# ELC0102_-_Green_Digits.net
KiCad netlist of a schematic drawn in Altium Designer
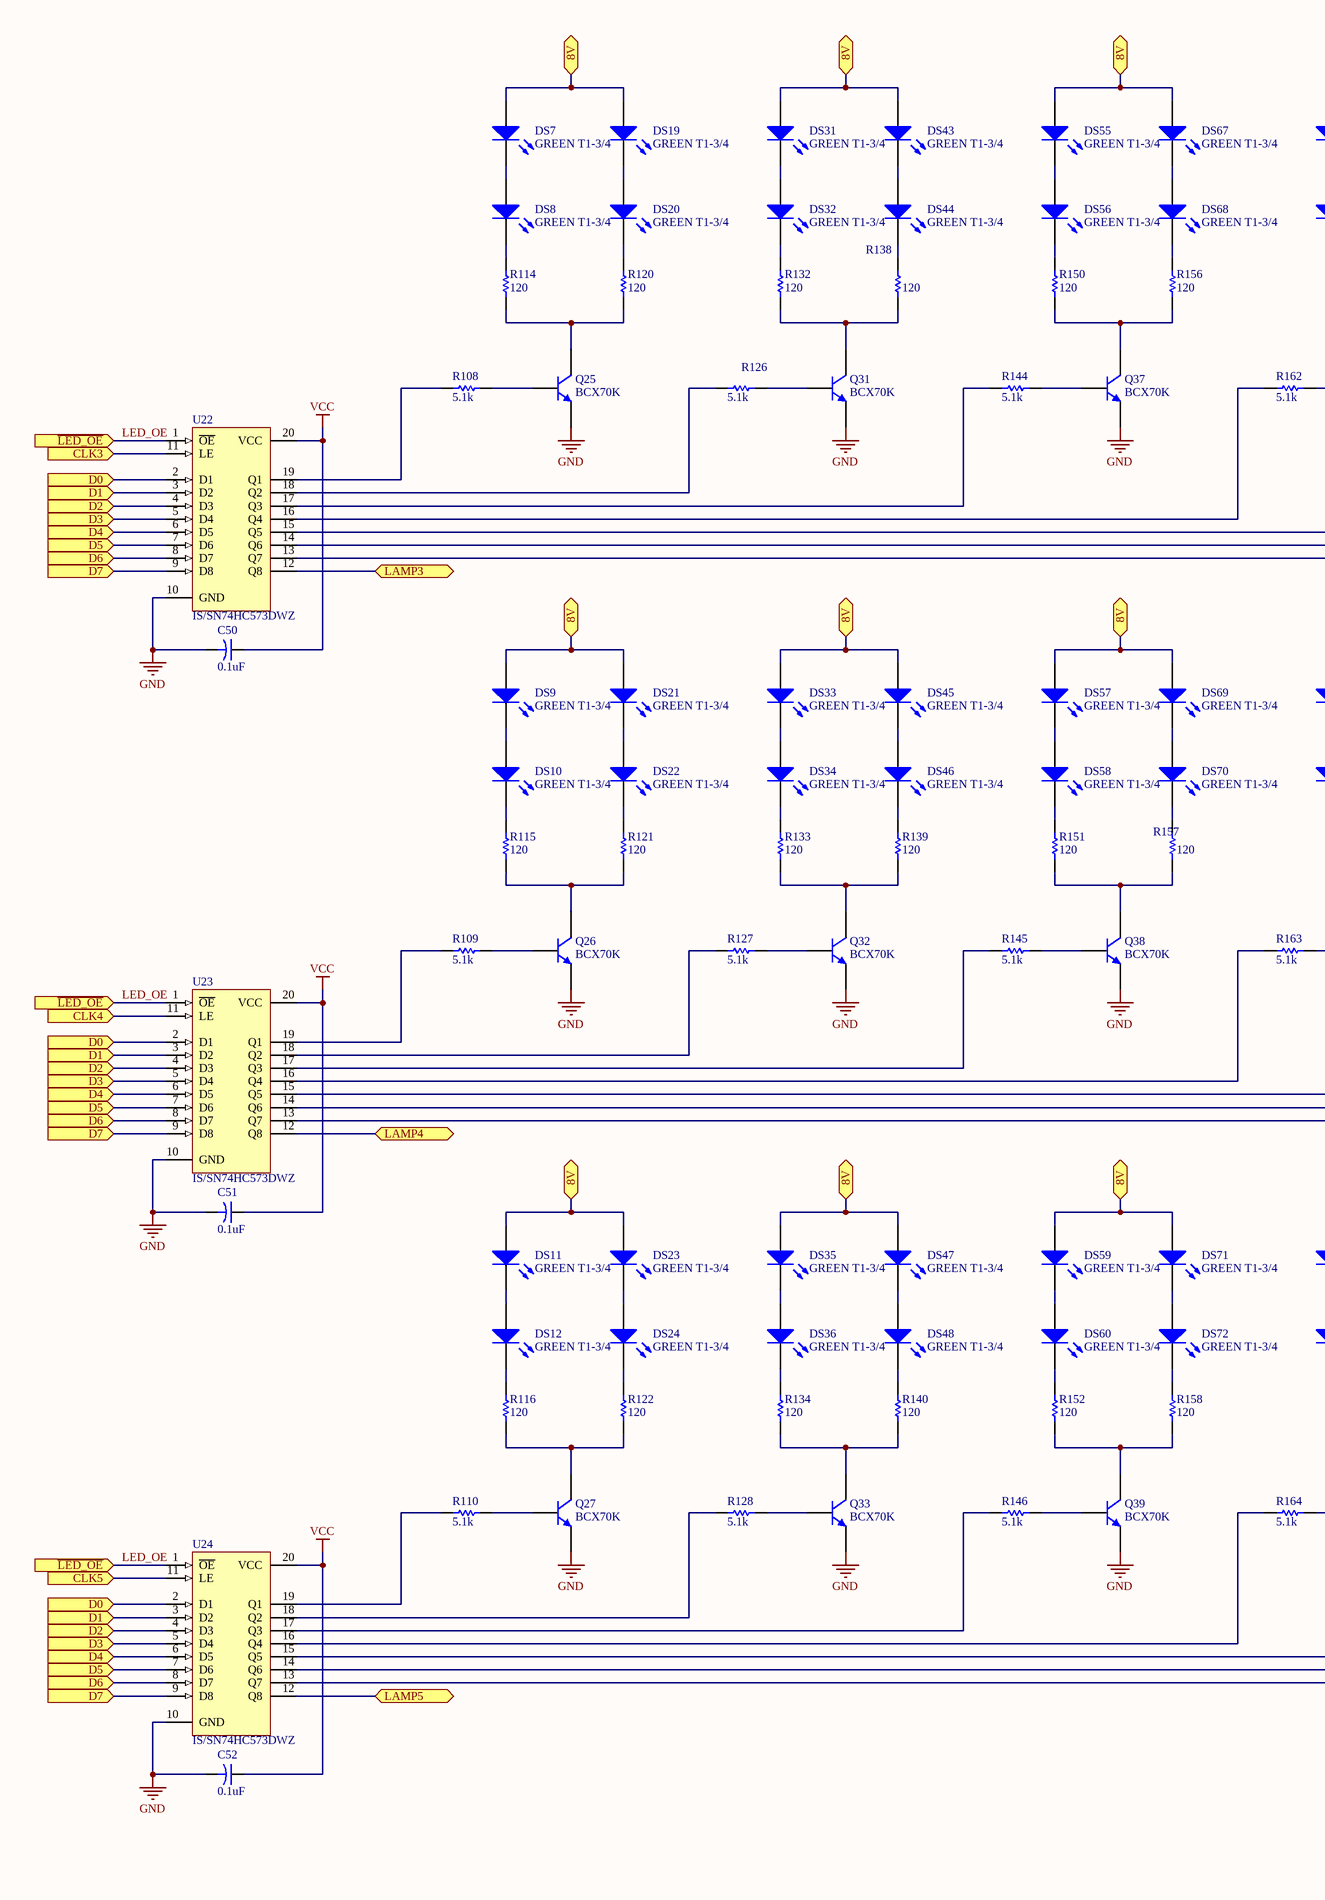
[diagram p0: ELC0102 - Green Digits.SchDoc, left]
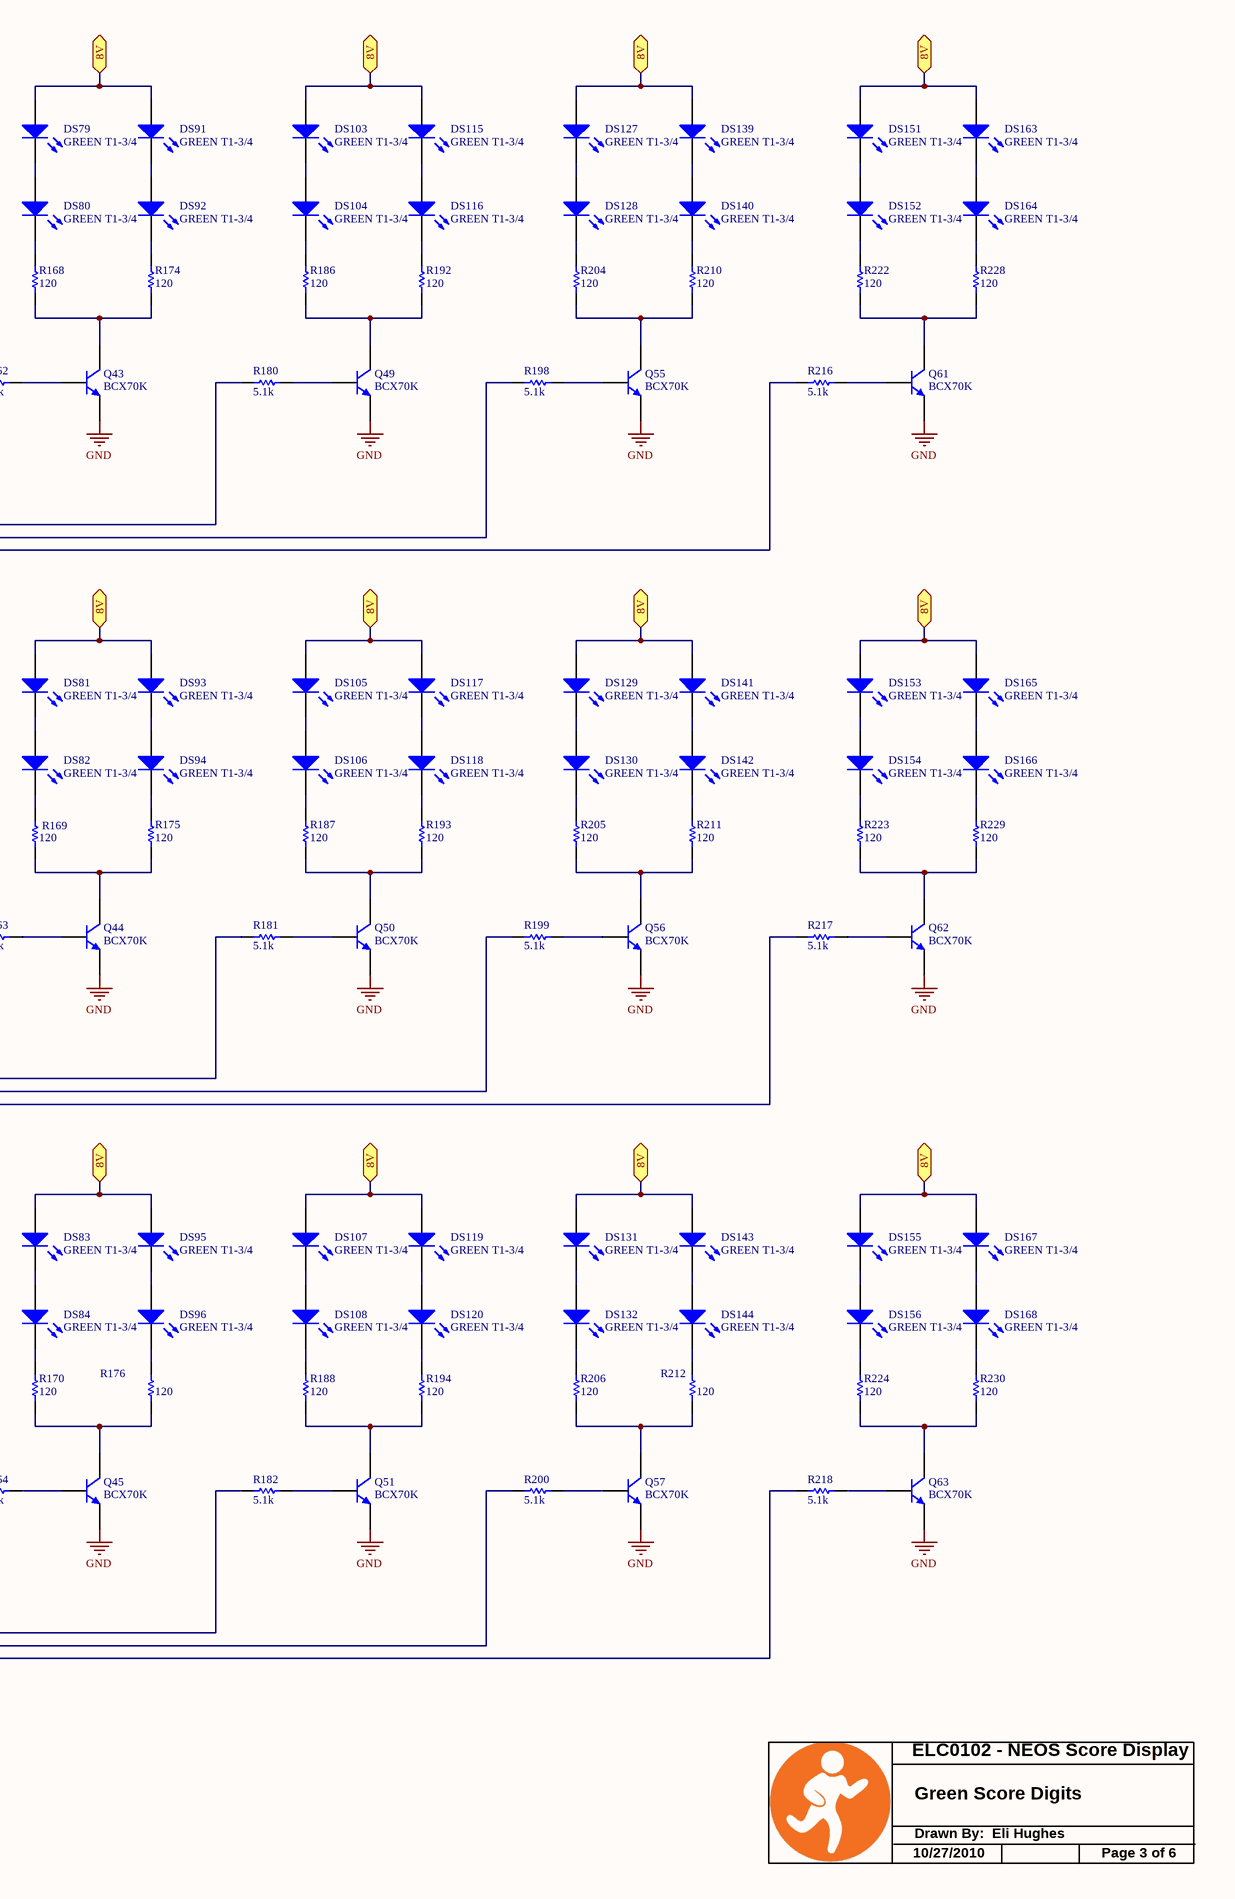
[diagram p1: ELC0102 - Green Digits.SchDoc, right]

(export (version "E")
  (design (tool "Eeschema 10.0.6"))
  (components
    (comp (ref "C50")
      (value "0.1uF")
      (footprint "C0805")
      (description "CAP .10UF 50V CERAMIC X7R 0805")
      (fields
        (field (name "MANUFACTURER") "Kemet")
        (field (name "MANUFACTURER PART NUMBER") "C0805C104K5RACTU")
        (field (name "SOURCE") "Digikey")
      )
      (libsource (lib "ELC102 - Scoreboard") (part "CS/C0805C104K5RACK"))
    )
    (comp (ref "C51")
      (value "0.1uF")
      (footprint "C0805")
      (description "CAP .10UF 50V CERAMIC X7R 0805")
      (fields
        (field (name "MANUFACTURER") "Kemet")
        (field (name "MANUFACTURER PART NUMBER") "C0805C104K5RACTU")
        (field (name "SOURCE") "Digikey")
      )
      (libsource (lib "ELC102 - Scoreboard") (part "CS/C0805C104K5RACK"))
    )
    (comp (ref "C52")
      (value "0.1uF")
      (footprint "C0805")
      (description "CAP .10UF 50V CERAMIC X7R 0805")
      (fields
        (field (name "MANUFACTURER") "Kemet")
        (field (name "MANUFACTURER PART NUMBER") "C0805C104K5RACTU")
        (field (name "SOURCE") "Digikey")
      )
      (libsource (lib "ELC102 - Scoreboard") (part "CS/C0805C104K5RACK"))
    )
    (comp (ref "DS7")
      (value "GREEN T1-3/4")
      (footprint "LED T1-3/4 Flush")
      (description "Optek LED Green/Clear High Brightness T1-3/4")
      (fields
        (field (name "MANUFACTURER") "OPTEK")
        (field (name "MANUFACTURER PART NUMBER") "OVLFG3C7")
        (field (name "SOURCE") "Digikey")
      )
      (libsource (lib "ScoreBoard") (part "LGCOVLFG3C7Z"))
    )
    (comp (ref "DS8")
      (value "GREEN T1-3/4")
      (footprint "LED T1-3/4 Flush")
      (description "Optek LED Green/Clear High Brightness T1-3/4")
      (fields
        (field (name "MANUFACTURER") "OPTEK")
        (field (name "MANUFACTURER PART NUMBER") "OVLFG3C7")
        (field (name "SOURCE") "Digikey")
      )
      (libsource (lib "ScoreBoard") (part "LGCOVLFG3C7Z"))
    )
    (comp (ref "DS9")
      (value "GREEN T1-3/4")
      (footprint "LED T1-3/4 Flush")
      (description "Optek LED Green/Clear High Brightness T1-3/4")
      (fields
        (field (name "MANUFACTURER") "OPTEK")
        (field (name "MANUFACTURER PART NUMBER") "OVLFG3C7")
        (field (name "SOURCE") "Digikey")
      )
      (libsource (lib "ScoreBoard") (part "LGCOVLFG3C7Z"))
    )
    (comp (ref "DS10")
      (value "GREEN T1-3/4")
      (footprint "LED T1-3/4 Flush")
      (description "Optek LED Green/Clear High Brightness T1-3/4")
      (fields
        (field (name "MANUFACTURER") "OPTEK")
        (field (name "MANUFACTURER PART NUMBER") "OVLFG3C7")
        (field (name "SOURCE") "Digikey")
      )
      (libsource (lib "ScoreBoard") (part "LGCOVLFG3C7Z"))
    )
    (comp (ref "DS11")
      (value "GREEN T1-3/4")
      (footprint "LED T1-3/4 Flush")
      (description "Optek LED Green/Clear High Brightness T1-3/4")
      (fields
        (field (name "MANUFACTURER") "OPTEK")
        (field (name "MANUFACTURER PART NUMBER") "OVLFG3C7")
        (field (name "SOURCE") "Digikey")
      )
      (libsource (lib "ScoreBoard") (part "LGCOVLFG3C7Z"))
    )
    (comp (ref "DS12")
      (value "GREEN T1-3/4")
      (footprint "LED T1-3/4 Flush")
      (description "Optek LED Green/Clear High Brightness T1-3/4")
      (fields
        (field (name "MANUFACTURER") "OPTEK")
        (field (name "MANUFACTURER PART NUMBER") "OVLFG3C7")
        (field (name "SOURCE") "Digikey")
      )
      (libsource (lib "ScoreBoard") (part "LGCOVLFG3C7Z"))
    )
    (comp (ref "DS19")
      (value "GREEN T1-3/4")
      (footprint "LED T1-3/4 Flush")
      (description "Optek LED Green/Clear High Brightness T1-3/4")
      (fields
        (field (name "MANUFACTURER") "OPTEK")
        (field (name "MANUFACTURER PART NUMBER") "OVLFG3C7")
        (field (name "SOURCE") "Digikey")
      )
      (libsource (lib "ScoreBoard") (part "LGCOVLFG3C7Z"))
    )
    (comp (ref "DS20")
      (value "GREEN T1-3/4")
      (footprint "LED T1-3/4 Flush")
      (description "Optek LED Green/Clear High Brightness T1-3/4")
      (fields
        (field (name "MANUFACTURER") "OPTEK")
        (field (name "MANUFACTURER PART NUMBER") "OVLFG3C7")
        (field (name "SOURCE") "Digikey")
      )
      (libsource (lib "ScoreBoard") (part "LGCOVLFG3C7Z"))
    )
    (comp (ref "DS21")
      (value "GREEN T1-3/4")
      (footprint "LED T1-3/4 Flush")
      (description "Optek LED Green/Clear High Brightness T1-3/4")
      (fields
        (field (name "MANUFACTURER") "OPTEK")
        (field (name "MANUFACTURER PART NUMBER") "OVLFG3C7")
        (field (name "SOURCE") "Digikey")
      )
      (libsource (lib "ScoreBoard") (part "LGCOVLFG3C7Z"))
    )
    (comp (ref "DS22")
      (value "GREEN T1-3/4")
      (footprint "LED T1-3/4 Flush")
      (description "Optek LED Green/Clear High Brightness T1-3/4")
      (fields
        (field (name "MANUFACTURER") "OPTEK")
        (field (name "MANUFACTURER PART NUMBER") "OVLFG3C7")
        (field (name "SOURCE") "Digikey")
      )
      (libsource (lib "ScoreBoard") (part "LGCOVLFG3C7Z"))
    )
    (comp (ref "DS23")
      (value "GREEN T1-3/4")
      (footprint "LED T1-3/4 Flush")
      (description "Optek LED Green/Clear High Brightness T1-3/4")
      (fields
        (field (name "MANUFACTURER") "OPTEK")
        (field (name "MANUFACTURER PART NUMBER") "OVLFG3C7")
        (field (name "SOURCE") "Digikey")
      )
      (libsource (lib "ScoreBoard") (part "LGCOVLFG3C7Z"))
    )
    (comp (ref "DS24")
      (value "GREEN T1-3/4")
      (footprint "LED T1-3/4 Flush")
      (description "Optek LED Green/Clear High Brightness T1-3/4")
      (fields
        (field (name "MANUFACTURER") "OPTEK")
        (field (name "MANUFACTURER PART NUMBER") "OVLFG3C7")
        (field (name "SOURCE") "Digikey")
      )
      (libsource (lib "ScoreBoard") (part "LGCOVLFG3C7Z"))
    )
    (comp (ref "DS31")
      (value "GREEN T1-3/4")
      (footprint "LED T1-3/4 Flush")
      (description "Optek LED Green/Clear High Brightness T1-3/4")
      (fields
        (field (name "MANUFACTURER") "OPTEK")
        (field (name "MANUFACTURER PART NUMBER") "OVLFG3C7")
        (field (name "SOURCE") "Digikey")
      )
      (libsource (lib "ScoreBoard") (part "LGCOVLFG3C7Z"))
    )
    (comp (ref "DS32")
      (value "GREEN T1-3/4")
      (footprint "LED T1-3/4 Flush")
      (description "Optek LED Green/Clear High Brightness T1-3/4")
      (fields
        (field (name "MANUFACTURER") "OPTEK")
        (field (name "MANUFACTURER PART NUMBER") "OVLFG3C7")
        (field (name "SOURCE") "Digikey")
      )
      (libsource (lib "ScoreBoard") (part "LGCOVLFG3C7Z"))
    )
    (comp (ref "DS33")
      (value "GREEN T1-3/4")
      (footprint "LED T1-3/4 Flush")
      (description "Optek LED Green/Clear High Brightness T1-3/4")
      (fields
        (field (name "MANUFACTURER") "OPTEK")
        (field (name "MANUFACTURER PART NUMBER") "OVLFG3C7")
        (field (name "SOURCE") "Digikey")
      )
      (libsource (lib "ScoreBoard") (part "LGCOVLFG3C7Z"))
    )
    (comp (ref "DS34")
      (value "GREEN T1-3/4")
      (footprint "LED T1-3/4 Flush")
      (description "Optek LED Green/Clear High Brightness T1-3/4")
      (fields
        (field (name "MANUFACTURER") "OPTEK")
        (field (name "MANUFACTURER PART NUMBER") "OVLFG3C7")
        (field (name "SOURCE") "Digikey")
      )
      (libsource (lib "ScoreBoard") (part "LGCOVLFG3C7Z"))
    )
    (comp (ref "DS35")
      (value "GREEN T1-3/4")
      (footprint "LED T1-3/4 Flush")
      (description "Optek LED Green/Clear High Brightness T1-3/4")
      (fields
        (field (name "MANUFACTURER") "OPTEK")
        (field (name "MANUFACTURER PART NUMBER") "OVLFG3C7")
        (field (name "SOURCE") "Digikey")
      )
      (libsource (lib "ScoreBoard") (part "LGCOVLFG3C7Z"))
    )
    (comp (ref "DS36")
      (value "GREEN T1-3/4")
      (footprint "LED T1-3/4 Flush")
      (description "Optek LED Green/Clear High Brightness T1-3/4")
      (fields
        (field (name "MANUFACTURER") "OPTEK")
        (field (name "MANUFACTURER PART NUMBER") "OVLFG3C7")
        (field (name "SOURCE") "Digikey")
      )
      (libsource (lib "ScoreBoard") (part "LGCOVLFG3C7Z"))
    )
    (comp (ref "DS43")
      (value "GREEN T1-3/4")
      (footprint "LED T1-3/4 Flush")
      (description "Optek LED Green/Clear High Brightness T1-3/4")
      (fields
        (field (name "MANUFACTURER") "OPTEK")
        (field (name "MANUFACTURER PART NUMBER") "OVLFG3C7")
        (field (name "SOURCE") "Digikey")
      )
      (libsource (lib "ScoreBoard") (part "LGCOVLFG3C7Z"))
    )
    (comp (ref "DS44")
      (value "GREEN T1-3/4")
      (footprint "LED T1-3/4 Flush")
      (description "Optek LED Green/Clear High Brightness T1-3/4")
      (fields
        (field (name "MANUFACTURER") "OPTEK")
        (field (name "MANUFACTURER PART NUMBER") "OVLFG3C7")
        (field (name "SOURCE") "Digikey")
      )
      (libsource (lib "ScoreBoard") (part "LGCOVLFG3C7Z"))
    )
    (comp (ref "DS45")
      (value "GREEN T1-3/4")
      (footprint "LED T1-3/4 Flush")
      (description "Optek LED Green/Clear High Brightness T1-3/4")
      (fields
        (field (name "MANUFACTURER") "OPTEK")
        (field (name "MANUFACTURER PART NUMBER") "OVLFG3C7")
        (field (name "SOURCE") "Digikey")
      )
      (libsource (lib "ScoreBoard") (part "LGCOVLFG3C7Z"))
    )
    (comp (ref "DS46")
      (value "GREEN T1-3/4")
      (footprint "LED T1-3/4 Flush")
      (description "Optek LED Green/Clear High Brightness T1-3/4")
      (fields
        (field (name "MANUFACTURER") "OPTEK")
        (field (name "MANUFACTURER PART NUMBER") "OVLFG3C7")
        (field (name "SOURCE") "Digikey")
      )
      (libsource (lib "ScoreBoard") (part "LGCOVLFG3C7Z"))
    )
    (comp (ref "DS47")
      (value "GREEN T1-3/4")
      (footprint "LED T1-3/4 Flush")
      (description "Optek LED Green/Clear High Brightness T1-3/4")
      (fields
        (field (name "MANUFACTURER") "OPTEK")
        (field (name "MANUFACTURER PART NUMBER") "OVLFG3C7")
        (field (name "SOURCE") "Digikey")
      )
      (libsource (lib "ScoreBoard") (part "LGCOVLFG3C7Z"))
    )
    (comp (ref "DS48")
      (value "GREEN T1-3/4")
      (footprint "LED T1-3/4 Flush")
      (description "Optek LED Green/Clear High Brightness T1-3/4")
      (fields
        (field (name "MANUFACTURER") "OPTEK")
        (field (name "MANUFACTURER PART NUMBER") "OVLFG3C7")
        (field (name "SOURCE") "Digikey")
      )
      (libsource (lib "ScoreBoard") (part "LGCOVLFG3C7Z"))
    )
    (comp (ref "DS55")
      (value "GREEN T1-3/4")
      (footprint "LED T1-3/4 Flush")
      (description "Optek LED Green/Clear High Brightness T1-3/4")
      (fields
        (field (name "MANUFACTURER") "OPTEK")
        (field (name "MANUFACTURER PART NUMBER") "OVLFG3C7")
        (field (name "SOURCE") "Digikey")
      )
      (libsource (lib "ScoreBoard") (part "LGCOVLFG3C7Z"))
    )
    (comp (ref "DS56")
      (value "GREEN T1-3/4")
      (footprint "LED T1-3/4 Flush")
      (description "Optek LED Green/Clear High Brightness T1-3/4")
      (fields
        (field (name "MANUFACTURER") "OPTEK")
        (field (name "MANUFACTURER PART NUMBER") "OVLFG3C7")
        (field (name "SOURCE") "Digikey")
      )
      (libsource (lib "ScoreBoard") (part "LGCOVLFG3C7Z"))
    )
    (comp (ref "DS57")
      (value "GREEN T1-3/4")
      (footprint "LED T1-3/4 Flush")
      (description "Optek LED Green/Clear High Brightness T1-3/4")
      (fields
        (field (name "MANUFACTURER") "OPTEK")
        (field (name "MANUFACTURER PART NUMBER") "OVLFG3C7")
        (field (name "SOURCE") "Digikey")
      )
      (libsource (lib "ScoreBoard") (part "LGCOVLFG3C7Z"))
    )
    (comp (ref "DS58")
      (value "GREEN T1-3/4")
      (footprint "LED T1-3/4 Flush")
      (description "Optek LED Green/Clear High Brightness T1-3/4")
      (fields
        (field (name "MANUFACTURER") "OPTEK")
        (field (name "MANUFACTURER PART NUMBER") "OVLFG3C7")
        (field (name "SOURCE") "Digikey")
      )
      (libsource (lib "ScoreBoard") (part "LGCOVLFG3C7Z"))
    )
    (comp (ref "DS59")
      (value "GREEN T1-3/4")
      (footprint "LED T1-3/4 Flush")
      (description "Optek LED Green/Clear High Brightness T1-3/4")
      (fields
        (field (name "MANUFACTURER") "OPTEK")
        (field (name "MANUFACTURER PART NUMBER") "OVLFG3C7")
        (field (name "SOURCE") "Digikey")
      )
      (libsource (lib "ScoreBoard") (part "LGCOVLFG3C7Z"))
    )
    (comp (ref "DS60")
      (value "GREEN T1-3/4")
      (footprint "LED T1-3/4 Flush")
      (description "Optek LED Green/Clear High Brightness T1-3/4")
      (fields
        (field (name "MANUFACTURER") "OPTEK")
        (field (name "MANUFACTURER PART NUMBER") "OVLFG3C7")
        (field (name "SOURCE") "Digikey")
      )
      (libsource (lib "ScoreBoard") (part "LGCOVLFG3C7Z"))
    )
    (comp (ref "DS67")
      (value "GREEN T1-3/4")
      (footprint "LED T1-3/4 Flush")
      (description "Optek LED Green/Clear High Brightness T1-3/4")
      (fields
        (field (name "MANUFACTURER") "OPTEK")
        (field (name "MANUFACTURER PART NUMBER") "OVLFG3C7")
        (field (name "SOURCE") "Digikey")
      )
      (libsource (lib "ScoreBoard") (part "LGCOVLFG3C7Z"))
    )
    (comp (ref "DS68")
      (value "GREEN T1-3/4")
      (footprint "LED T1-3/4 Flush")
      (description "Optek LED Green/Clear High Brightness T1-3/4")
      (fields
        (field (name "MANUFACTURER") "OPTEK")
        (field (name "MANUFACTURER PART NUMBER") "OVLFG3C7")
        (field (name "SOURCE") "Digikey")
      )
      (libsource (lib "ScoreBoard") (part "LGCOVLFG3C7Z"))
    )
    (comp (ref "DS69")
      (value "GREEN T1-3/4")
      (footprint "LED T1-3/4 Flush")
      (description "Optek LED Green/Clear High Brightness T1-3/4")
      (fields
        (field (name "MANUFACTURER") "OPTEK")
        (field (name "MANUFACTURER PART NUMBER") "OVLFG3C7")
        (field (name "SOURCE") "Digikey")
      )
      (libsource (lib "ScoreBoard") (part "LGCOVLFG3C7Z"))
    )
    (comp (ref "DS70")
      (value "GREEN T1-3/4")
      (footprint "LED T1-3/4 Flush")
      (description "Optek LED Green/Clear High Brightness T1-3/4")
      (fields
        (field (name "MANUFACTURER") "OPTEK")
        (field (name "MANUFACTURER PART NUMBER") "OVLFG3C7")
        (field (name "SOURCE") "Digikey")
      )
      (libsource (lib "ScoreBoard") (part "LGCOVLFG3C7Z"))
    )
    (comp (ref "DS71")
      (value "GREEN T1-3/4")
      (footprint "LED T1-3/4 Flush")
      (description "Optek LED Green/Clear High Brightness T1-3/4")
      (fields
        (field (name "MANUFACTURER") "OPTEK")
        (field (name "MANUFACTURER PART NUMBER") "OVLFG3C7")
        (field (name "SOURCE") "Digikey")
      )
      (libsource (lib "ScoreBoard") (part "LGCOVLFG3C7Z"))
    )
    (comp (ref "DS72")
      (value "GREEN T1-3/4")
      (footprint "LED T1-3/4 Flush")
      (description "Optek LED Green/Clear High Brightness T1-3/4")
      (fields
        (field (name "MANUFACTURER") "OPTEK")
        (field (name "MANUFACTURER PART NUMBER") "OVLFG3C7")
        (field (name "SOURCE") "Digikey")
      )
      (libsource (lib "ScoreBoard") (part "LGCOVLFG3C7Z"))
    )
    (comp (ref "DS79")
      (value "GREEN T1-3/4")
      (footprint "LED T1-3/4 Flush")
      (description "Optek LED Green/Clear High Brightness T1-3/4")
      (fields
        (field (name "MANUFACTURER") "OPTEK")
        (field (name "MANUFACTURER PART NUMBER") "OVLFG3C7")
        (field (name "SOURCE") "Digikey")
      )
      (libsource (lib "ScoreBoard") (part "LGCOVLFG3C7Z"))
    )
    (comp (ref "DS80")
      (value "GREEN T1-3/4")
      (footprint "LED T1-3/4 Flush")
      (description "Optek LED Green/Clear High Brightness T1-3/4")
      (fields
        (field (name "MANUFACTURER") "OPTEK")
        (field (name "MANUFACTURER PART NUMBER") "OVLFG3C7")
        (field (name "SOURCE") "Digikey")
      )
      (libsource (lib "ScoreBoard") (part "LGCOVLFG3C7Z"))
    )
    (comp (ref "DS81")
      (value "GREEN T1-3/4")
      (footprint "LED T1-3/4 Flush")
      (description "Optek LED Green/Clear High Brightness T1-3/4")
      (fields
        (field (name "MANUFACTURER") "OPTEK")
        (field (name "MANUFACTURER PART NUMBER") "OVLFG3C7")
        (field (name "SOURCE") "Digikey")
      )
      (libsource (lib "ScoreBoard") (part "LGCOVLFG3C7Z"))
    )
    (comp (ref "DS82")
      (value "GREEN T1-3/4")
      (footprint "LED T1-3/4 Flush")
      (description "Optek LED Green/Clear High Brightness T1-3/4")
      (fields
        (field (name "MANUFACTURER") "OPTEK")
        (field (name "MANUFACTURER PART NUMBER") "OVLFG3C7")
        (field (name "SOURCE") "Digikey")
      )
      (libsource (lib "ScoreBoard") (part "LGCOVLFG3C7Z"))
    )
    (comp (ref "DS83")
      (value "GREEN T1-3/4")
      (footprint "LED T1-3/4 Flush")
      (description "Optek LED Green/Clear High Brightness T1-3/4")
      (fields
        (field (name "MANUFACTURER") "OPTEK")
        (field (name "MANUFACTURER PART NUMBER") "OVLFG3C7")
        (field (name "SOURCE") "Digikey")
      )
      (libsource (lib "ScoreBoard") (part "LGCOVLFG3C7Z"))
    )
    (comp (ref "DS84")
      (value "GREEN T1-3/4")
      (footprint "LED T1-3/4 Flush")
      (description "Optek LED Green/Clear High Brightness T1-3/4")
      (fields
        (field (name "MANUFACTURER") "OPTEK")
        (field (name "MANUFACTURER PART NUMBER") "OVLFG3C7")
        (field (name "SOURCE") "Digikey")
      )
      (libsource (lib "ScoreBoard") (part "LGCOVLFG3C7Z"))
    )
    (comp (ref "DS91")
      (value "GREEN T1-3/4")
      (footprint "LED T1-3/4 Flush")
      (description "Optek LED Green/Clear High Brightness T1-3/4")
      (fields
        (field (name "MANUFACTURER") "OPTEK")
        (field (name "MANUFACTURER PART NUMBER") "OVLFG3C7")
        (field (name "SOURCE") "Digikey")
      )
      (libsource (lib "ScoreBoard") (part "LGCOVLFG3C7Z"))
    )
    (comp (ref "DS92")
      (value "GREEN T1-3/4")
      (footprint "LED T1-3/4 Flush")
      (description "Optek LED Green/Clear High Brightness T1-3/4")
      (fields
        (field (name "MANUFACTURER") "OPTEK")
        (field (name "MANUFACTURER PART NUMBER") "OVLFG3C7")
        (field (name "SOURCE") "Digikey")
      )
      (libsource (lib "ScoreBoard") (part "LGCOVLFG3C7Z"))
    )
    (comp (ref "DS93")
      (value "GREEN T1-3/4")
      (footprint "LED T1-3/4 Flush")
      (description "Optek LED Green/Clear High Brightness T1-3/4")
      (fields
        (field (name "MANUFACTURER") "OPTEK")
        (field (name "MANUFACTURER PART NUMBER") "OVLFG3C7")
        (field (name "SOURCE") "Digikey")
      )
      (libsource (lib "ScoreBoard") (part "LGCOVLFG3C7Z"))
    )
    (comp (ref "DS94")
      (value "GREEN T1-3/4")
      (footprint "LED T1-3/4 Flush")
      (description "Optek LED Green/Clear High Brightness T1-3/4")
      (fields
        (field (name "MANUFACTURER") "OPTEK")
        (field (name "MANUFACTURER PART NUMBER") "OVLFG3C7")
        (field (name "SOURCE") "Digikey")
      )
      (libsource (lib "ScoreBoard") (part "LGCOVLFG3C7Z"))
    )
    (comp (ref "DS95")
      (value "GREEN T1-3/4")
      (footprint "LED T1-3/4 Flush")
      (description "Optek LED Green/Clear High Brightness T1-3/4")
      (fields
        (field (name "MANUFACTURER") "OPTEK")
        (field (name "MANUFACTURER PART NUMBER") "OVLFG3C7")
        (field (name "SOURCE") "Digikey")
      )
      (libsource (lib "ScoreBoard") (part "LGCOVLFG3C7Z"))
    )
    (comp (ref "DS96")
      (value "GREEN T1-3/4")
      (footprint "LED T1-3/4 Flush")
      (description "Optek LED Green/Clear High Brightness T1-3/4")
      (fields
        (field (name "MANUFACTURER") "OPTEK")
        (field (name "MANUFACTURER PART NUMBER") "OVLFG3C7")
        (field (name "SOURCE") "Digikey")
      )
      (libsource (lib "ScoreBoard") (part "LGCOVLFG3C7Z"))
    )
    (comp (ref "DS103")
      (value "GREEN T1-3/4")
      (footprint "LED T1-3/4 Flush")
      (description "Optek LED Green/Clear High Brightness T1-3/4")
      (fields
        (field (name "MANUFACTURER") "OPTEK")
        (field (name "MANUFACTURER PART NUMBER") "OVLFG3C7")
        (field (name "SOURCE") "Digikey")
      )
      (libsource (lib "ScoreBoard") (part "LGCOVLFG3C7Z"))
    )
    (comp (ref "DS104")
      (value "GREEN T1-3/4")
      (footprint "LED T1-3/4 Flush")
      (description "Optek LED Green/Clear High Brightness T1-3/4")
      (fields
        (field (name "MANUFACTURER") "OPTEK")
        (field (name "MANUFACTURER PART NUMBER") "OVLFG3C7")
        (field (name "SOURCE") "Digikey")
      )
      (libsource (lib "ScoreBoard") (part "LGCOVLFG3C7Z"))
    )
    (comp (ref "DS105")
      (value "GREEN T1-3/4")
      (footprint "LED T1-3/4 Flush")
      (description "Optek LED Green/Clear High Brightness T1-3/4")
      (fields
        (field (name "MANUFACTURER") "OPTEK")
        (field (name "MANUFACTURER PART NUMBER") "OVLFG3C7")
        (field (name "SOURCE") "Digikey")
      )
      (libsource (lib "ScoreBoard") (part "LGCOVLFG3C7Z"))
    )
    (comp (ref "DS106")
      (value "GREEN T1-3/4")
      (footprint "LED T1-3/4 Flush")
      (description "Optek LED Green/Clear High Brightness T1-3/4")
      (fields
        (field (name "MANUFACTURER") "OPTEK")
        (field (name "MANUFACTURER PART NUMBER") "OVLFG3C7")
        (field (name "SOURCE") "Digikey")
      )
      (libsource (lib "ScoreBoard") (part "LGCOVLFG3C7Z"))
    )
    (comp (ref "DS107")
      (value "GREEN T1-3/4")
      (footprint "LED T1-3/4 Flush")
      (description "Optek LED Green/Clear High Brightness T1-3/4")
      (fields
        (field (name "MANUFACTURER") "OPTEK")
        (field (name "MANUFACTURER PART NUMBER") "OVLFG3C7")
        (field (name "SOURCE") "Digikey")
      )
      (libsource (lib "ScoreBoard") (part "LGCOVLFG3C7Z"))
    )
    (comp (ref "DS108")
      (value "GREEN T1-3/4")
      (footprint "LED T1-3/4 Flush")
      (description "Optek LED Green/Clear High Brightness T1-3/4")
      (fields
        (field (name "MANUFACTURER") "OPTEK")
        (field (name "MANUFACTURER PART NUMBER") "OVLFG3C7")
        (field (name "SOURCE") "Digikey")
      )
      (libsource (lib "ScoreBoard") (part "LGCOVLFG3C7Z"))
    )
    (comp (ref "DS115")
      (value "GREEN T1-3/4")
      (footprint "LED T1-3/4 Flush")
      (description "Optek LED Green/Clear High Brightness T1-3/4")
      (fields
        (field (name "MANUFACTURER") "OPTEK")
        (field (name "MANUFACTURER PART NUMBER") "OVLFG3C7")
        (field (name "SOURCE") "Digikey")
      )
      (libsource (lib "ScoreBoard") (part "LGCOVLFG3C7Z"))
    )
    (comp (ref "DS116")
      (value "GREEN T1-3/4")
      (footprint "LED T1-3/4 Flush")
      (description "Optek LED Green/Clear High Brightness T1-3/4")
      (fields
        (field (name "MANUFACTURER") "OPTEK")
        (field (name "MANUFACTURER PART NUMBER") "OVLFG3C7")
        (field (name "SOURCE") "Digikey")
      )
      (libsource (lib "ScoreBoard") (part "LGCOVLFG3C7Z"))
    )
    (comp (ref "DS117")
      (value "GREEN T1-3/4")
      (footprint "LED T1-3/4 Flush")
      (description "Optek LED Green/Clear High Brightness T1-3/4")
      (fields
        (field (name "MANUFACTURER") "OPTEK")
        (field (name "MANUFACTURER PART NUMBER") "OVLFG3C7")
        (field (name "SOURCE") "Digikey")
      )
      (libsource (lib "ScoreBoard") (part "LGCOVLFG3C7Z"))
    )
    (comp (ref "DS118")
      (value "GREEN T1-3/4")
      (footprint "LED T1-3/4 Flush")
      (description "Optek LED Green/Clear High Brightness T1-3/4")
      (fields
        (field (name "MANUFACTURER") "OPTEK")
        (field (name "MANUFACTURER PART NUMBER") "OVLFG3C7")
        (field (name "SOURCE") "Digikey")
      )
      (libsource (lib "ScoreBoard") (part "LGCOVLFG3C7Z"))
    )
    (comp (ref "DS119")
      (value "GREEN T1-3/4")
      (footprint "LED T1-3/4 Flush")
      (description "Optek LED Green/Clear High Brightness T1-3/4")
      (fields
        (field (name "MANUFACTURER") "OPTEK")
        (field (name "MANUFACTURER PART NUMBER") "OVLFG3C7")
        (field (name "SOURCE") "Digikey")
      )
      (libsource (lib "ScoreBoard") (part "LGCOVLFG3C7Z"))
    )
    (comp (ref "DS120")
      (value "GREEN T1-3/4")
      (footprint "LED T1-3/4 Flush")
      (description "Optek LED Green/Clear High Brightness T1-3/4")
      (fields
        (field (name "MANUFACTURER") "OPTEK")
        (field (name "MANUFACTURER PART NUMBER") "OVLFG3C7")
        (field (name "SOURCE") "Digikey")
      )
      (libsource (lib "ScoreBoard") (part "LGCOVLFG3C7Z"))
    )
    (comp (ref "DS127")
      (value "GREEN T1-3/4")
      (footprint "LED T1-3/4 Flush")
      (description "Optek LED Green/Clear High Brightness T1-3/4")
      (fields
        (field (name "MANUFACTURER") "OPTEK")
        (field (name "MANUFACTURER PART NUMBER") "OVLFG3C7")
        (field (name "SOURCE") "Digikey")
      )
      (libsource (lib "ScoreBoard") (part "LGCOVLFG3C7Z"))
    )
    (comp (ref "DS128")
      (value "GREEN T1-3/4")
      (footprint "LED T1-3/4 Flush")
      (description "Optek LED Green/Clear High Brightness T1-3/4")
      (fields
        (field (name "MANUFACTURER") "OPTEK")
        (field (name "MANUFACTURER PART NUMBER") "OVLFG3C7")
        (field (name "SOURCE") "Digikey")
      )
      (libsource (lib "ScoreBoard") (part "LGCOVLFG3C7Z"))
    )
    (comp (ref "DS129")
      (value "GREEN T1-3/4")
      (footprint "LED T1-3/4 Flush")
      (description "Optek LED Green/Clear High Brightness T1-3/4")
      (fields
        (field (name "MANUFACTURER") "OPTEK")
        (field (name "MANUFACTURER PART NUMBER") "OVLFG3C7")
        (field (name "SOURCE") "Digikey")
      )
      (libsource (lib "ScoreBoard") (part "LGCOVLFG3C7Z"))
    )
    (comp (ref "DS130")
      (value "GREEN T1-3/4")
      (footprint "LED T1-3/4 Flush")
      (description "Optek LED Green/Clear High Brightness T1-3/4")
      (fields
        (field (name "MANUFACTURER") "OPTEK")
        (field (name "MANUFACTURER PART NUMBER") "OVLFG3C7")
        (field (name "SOURCE") "Digikey")
      )
      (libsource (lib "ScoreBoard") (part "LGCOVLFG3C7Z"))
    )
    (comp (ref "DS131")
      (value "GREEN T1-3/4")
      (footprint "LED T1-3/4 Flush")
      (description "Optek LED Green/Clear High Brightness T1-3/4")
      (fields
        (field (name "MANUFACTURER") "OPTEK")
        (field (name "MANUFACTURER PART NUMBER") "OVLFG3C7")
        (field (name "SOURCE") "Digikey")
      )
      (libsource (lib "ScoreBoard") (part "LGCOVLFG3C7Z"))
    )
    (comp (ref "DS132")
      (value "GREEN T1-3/4")
      (footprint "LED T1-3/4 Flush")
      (description "Optek LED Green/Clear High Brightness T1-3/4")
      (fields
        (field (name "MANUFACTURER") "OPTEK")
        (field (name "MANUFACTURER PART NUMBER") "OVLFG3C7")
        (field (name "SOURCE") "Digikey")
      )
      (libsource (lib "ScoreBoard") (part "LGCOVLFG3C7Z"))
    )
    (comp (ref "DS139")
      (value "GREEN T1-3/4")
      (footprint "LED T1-3/4 Flush")
      (description "Optek LED Green/Clear High Brightness T1-3/4")
      (fields
        (field (name "MANUFACTURER") "OPTEK")
        (field (name "MANUFACTURER PART NUMBER") "OVLFG3C7")
        (field (name "SOURCE") "Digikey")
      )
      (libsource (lib "ScoreBoard") (part "LGCOVLFG3C7Z"))
    )
    (comp (ref "DS140")
      (value "GREEN T1-3/4")
      (footprint "LED T1-3/4 Flush")
      (description "Optek LED Green/Clear High Brightness T1-3/4")
      (fields
        (field (name "MANUFACTURER") "OPTEK")
        (field (name "MANUFACTURER PART NUMBER") "OVLFG3C7")
        (field (name "SOURCE") "Digikey")
      )
      (libsource (lib "ScoreBoard") (part "LGCOVLFG3C7Z"))
    )
    (comp (ref "DS141")
      (value "GREEN T1-3/4")
      (footprint "LED T1-3/4 Flush")
      (description "Optek LED Green/Clear High Brightness T1-3/4")
      (fields
        (field (name "MANUFACTURER") "OPTEK")
        (field (name "MANUFACTURER PART NUMBER") "OVLFG3C7")
        (field (name "SOURCE") "Digikey")
      )
      (libsource (lib "ScoreBoard") (part "LGCOVLFG3C7Z"))
    )
    (comp (ref "DS142")
      (value "GREEN T1-3/4")
      (footprint "LED T1-3/4 Flush")
      (description "Optek LED Green/Clear High Brightness T1-3/4")
      (fields
        (field (name "MANUFACTURER") "OPTEK")
        (field (name "MANUFACTURER PART NUMBER") "OVLFG3C7")
        (field (name "SOURCE") "Digikey")
      )
      (libsource (lib "ScoreBoard") (part "LGCOVLFG3C7Z"))
    )
    (comp (ref "DS143")
      (value "GREEN T1-3/4")
      (footprint "LED T1-3/4 Flush")
      (description "Optek LED Green/Clear High Brightness T1-3/4")
      (fields
        (field (name "MANUFACTURER") "OPTEK")
        (field (name "MANUFACTURER PART NUMBER") "OVLFG3C7")
        (field (name "SOURCE") "Digikey")
      )
      (libsource (lib "ScoreBoard") (part "LGCOVLFG3C7Z"))
    )
    (comp (ref "DS144")
      (value "GREEN T1-3/4")
      (footprint "LED T1-3/4 Flush")
      (description "Optek LED Green/Clear High Brightness T1-3/4")
      (fields
        (field (name "MANUFACTURER") "OPTEK")
        (field (name "MANUFACTURER PART NUMBER") "OVLFG3C7")
        (field (name "SOURCE") "Digikey")
      )
      (libsource (lib "ScoreBoard") (part "LGCOVLFG3C7Z"))
    )
    (comp (ref "DS151")
      (value "GREEN T1-3/4")
      (footprint "LED T1-3/4 Flush")
      (description "Optek LED Green/Clear High Brightness T1-3/4")
      (fields
        (field (name "MANUFACTURER") "OPTEK")
        (field (name "MANUFACTURER PART NUMBER") "OVLFG3C7")
        (field (name "SOURCE") "Digikey")
      )
      (libsource (lib "ScoreBoard") (part "LGCOVLFG3C7Z"))
    )
    (comp (ref "DS152")
      (value "GREEN T1-3/4")
      (footprint "LED T1-3/4 Flush")
      (description "Optek LED Green/Clear High Brightness T1-3/4")
      (fields
        (field (name "MANUFACTURER") "OPTEK")
        (field (name "MANUFACTURER PART NUMBER") "OVLFG3C7")
        (field (name "SOURCE") "Digikey")
      )
      (libsource (lib "ScoreBoard") (part "LGCOVLFG3C7Z"))
    )
    (comp (ref "DS153")
      (value "GREEN T1-3/4")
      (footprint "LED T1-3/4 Flush")
      (description "Optek LED Green/Clear High Brightness T1-3/4")
      (fields
        (field (name "MANUFACTURER") "OPTEK")
        (field (name "MANUFACTURER PART NUMBER") "OVLFG3C7")
        (field (name "SOURCE") "Digikey")
      )
      (libsource (lib "ScoreBoard") (part "LGCOVLFG3C7Z"))
    )
    (comp (ref "DS154")
      (value "GREEN T1-3/4")
      (footprint "LED T1-3/4 Flush")
      (description "Optek LED Green/Clear High Brightness T1-3/4")
      (fields
        (field (name "MANUFACTURER") "OPTEK")
        (field (name "MANUFACTURER PART NUMBER") "OVLFG3C7")
        (field (name "SOURCE") "Digikey")
      )
      (libsource (lib "ScoreBoard") (part "LGCOVLFG3C7Z"))
    )
    (comp (ref "DS155")
      (value "GREEN T1-3/4")
      (footprint "LED T1-3/4 Flush")
      (description "Optek LED Green/Clear High Brightness T1-3/4")
      (fields
        (field (name "MANUFACTURER") "OPTEK")
        (field (name "MANUFACTURER PART NUMBER") "OVLFG3C7")
        (field (name "SOURCE") "Digikey")
      )
      (libsource (lib "ScoreBoard") (part "LGCOVLFG3C7Z"))
    )
    (comp (ref "DS156")
      (value "GREEN T1-3/4")
      (footprint "LED T1-3/4 Flush")
      (description "Optek LED Green/Clear High Brightness T1-3/4")
      (fields
        (field (name "MANUFACTURER") "OPTEK")
        (field (name "MANUFACTURER PART NUMBER") "OVLFG3C7")
        (field (name "SOURCE") "Digikey")
      )
      (libsource (lib "ScoreBoard") (part "LGCOVLFG3C7Z"))
    )
    (comp (ref "DS163")
      (value "GREEN T1-3/4")
      (footprint "LED T1-3/4 Flush")
      (description "Optek LED Green/Clear High Brightness T1-3/4")
      (fields
        (field (name "MANUFACTURER") "OPTEK")
        (field (name "MANUFACTURER PART NUMBER") "OVLFG3C7")
        (field (name "SOURCE") "Digikey")
      )
      (libsource (lib "ScoreBoard") (part "LGCOVLFG3C7Z"))
    )
    (comp (ref "DS164")
      (value "GREEN T1-3/4")
      (footprint "LED T1-3/4 Flush")
      (description "Optek LED Green/Clear High Brightness T1-3/4")
      (fields
        (field (name "MANUFACTURER") "OPTEK")
        (field (name "MANUFACTURER PART NUMBER") "OVLFG3C7")
        (field (name "SOURCE") "Digikey")
      )
      (libsource (lib "ScoreBoard") (part "LGCOVLFG3C7Z"))
    )
    (comp (ref "DS165")
      (value "GREEN T1-3/4")
      (footprint "LED T1-3/4 Flush")
      (description "Optek LED Green/Clear High Brightness T1-3/4")
      (fields
        (field (name "MANUFACTURER") "OPTEK")
        (field (name "MANUFACTURER PART NUMBER") "OVLFG3C7")
        (field (name "SOURCE") "Digikey")
      )
      (libsource (lib "ScoreBoard") (part "LGCOVLFG3C7Z"))
    )
    (comp (ref "DS166")
      (value "GREEN T1-3/4")
      (footprint "LED T1-3/4 Flush")
      (description "Optek LED Green/Clear High Brightness T1-3/4")
      (fields
        (field (name "MANUFACTURER") "OPTEK")
        (field (name "MANUFACTURER PART NUMBER") "OVLFG3C7")
        (field (name "SOURCE") "Digikey")
      )
      (libsource (lib "ScoreBoard") (part "LGCOVLFG3C7Z"))
    )
    (comp (ref "DS167")
      (value "GREEN T1-3/4")
      (footprint "LED T1-3/4 Flush")
      (description "Optek LED Green/Clear High Brightness T1-3/4")
      (fields
        (field (name "MANUFACTURER") "OPTEK")
        (field (name "MANUFACTURER PART NUMBER") "OVLFG3C7")
        (field (name "SOURCE") "Digikey")
      )
      (libsource (lib "ScoreBoard") (part "LGCOVLFG3C7Z"))
    )
    (comp (ref "DS168")
      (value "GREEN T1-3/4")
      (footprint "LED T1-3/4 Flush")
      (description "Optek LED Green/Clear High Brightness T1-3/4")
      (fields
        (field (name "MANUFACTURER") "OPTEK")
        (field (name "MANUFACTURER PART NUMBER") "OVLFG3C7")
        (field (name "SOURCE") "Digikey")
      )
      (libsource (lib "ScoreBoard") (part "LGCOVLFG3C7Z"))
    )
    (comp (ref "Q25")
      (value "BCX70K")
      (footprint "SOT23")
      (description "TRANS NPN AF 45V SOT-23")
      (fields (field (name "MANUFACTURER") "Fairchild Semiconductor") (field (name "SOURCE") "Digikey"))
      (libsource (lib "ScoreBoard") (part "QS/BCX70K00Z"))
    )
    (comp (ref "Q26")
      (value "BCX70K")
      (footprint "SOT23")
      (description "TRANS NPN AF 45V SOT-23")
      (fields (field (name "MANUFACTURER") "Fairchild Semiconductor") (field (name "SOURCE") "Digikey"))
      (libsource (lib "ScoreBoard") (part "QS/BCX70K00Z"))
    )
    (comp (ref "Q27")
      (value "BCX70K")
      (footprint "SOT23")
      (description "TRANS NPN AF 45V SOT-23")
      (fields (field (name "MANUFACTURER") "Fairchild Semiconductor") (field (name "SOURCE") "Digikey"))
      (libsource (lib "ScoreBoard") (part "QS/BCX70K00Z"))
    )
    (comp (ref "Q31")
      (value "BCX70K")
      (footprint "SOT23")
      (description "TRANS NPN AF 45V SOT-23")
      (fields (field (name "MANUFACTURER") "Fairchild Semiconductor") (field (name "SOURCE") "Digikey"))
      (libsource (lib "ScoreBoard") (part "QS/BCX70K00Z"))
    )
    (comp (ref "Q32")
      (value "BCX70K")
      (footprint "SOT23")
      (description "TRANS NPN AF 45V SOT-23")
      (fields (field (name "MANUFACTURER") "Fairchild Semiconductor") (field (name "SOURCE") "Digikey"))
      (libsource (lib "ScoreBoard") (part "QS/BCX70K00Z"))
    )
    (comp (ref "Q33")
      (value "BCX70K")
      (footprint "SOT23")
      (description "TRANS NPN AF 45V SOT-23")
      (fields (field (name "MANUFACTURER") "Fairchild Semiconductor") (field (name "SOURCE") "Digikey"))
      (libsource (lib "ScoreBoard") (part "QS/BCX70K00Z"))
    )
    (comp (ref "Q37")
      (value "BCX70K")
      (footprint "SOT23")
      (description "TRANS NPN AF 45V SOT-23")
      (fields (field (name "MANUFACTURER") "Fairchild Semiconductor") (field (name "SOURCE") "Digikey"))
      (libsource (lib "ScoreBoard") (part "QS/BCX70K00Z"))
    )
    (comp (ref "Q38")
      (value "BCX70K")
      (footprint "SOT23")
      (description "TRANS NPN AF 45V SOT-23")
      (fields (field (name "MANUFACTURER") "Fairchild Semiconductor") (field (name "SOURCE") "Digikey"))
      (libsource (lib "ScoreBoard") (part "QS/BCX70K00Z"))
    )
    (comp (ref "Q39")
      (value "BCX70K")
      (footprint "SOT23")
      (description "TRANS NPN AF 45V SOT-23")
      (fields (field (name "MANUFACTURER") "Fairchild Semiconductor") (field (name "SOURCE") "Digikey"))
      (libsource (lib "ScoreBoard") (part "QS/BCX70K00Z"))
    )
    (comp (ref "Q43")
      (value "BCX70K")
      (footprint "SOT23")
      (description "TRANS NPN AF 45V SOT-23")
      (fields (field (name "MANUFACTURER") "Fairchild Semiconductor") (field (name "SOURCE") "Digikey"))
      (libsource (lib "ScoreBoard") (part "QS/BCX70K00Z"))
    )
    (comp (ref "Q44")
      (value "BCX70K")
      (footprint "SOT23")
      (description "TRANS NPN AF 45V SOT-23")
      (fields (field (name "MANUFACTURER") "Fairchild Semiconductor") (field (name "SOURCE") "Digikey"))
      (libsource (lib "ScoreBoard") (part "QS/BCX70K00Z"))
    )
    (comp (ref "Q45")
      (value "BCX70K")
      (footprint "SOT23")
      (description "TRANS NPN AF 45V SOT-23")
      (fields (field (name "MANUFACTURER") "Fairchild Semiconductor") (field (name "SOURCE") "Digikey"))
      (libsource (lib "ScoreBoard") (part "QS/BCX70K00Z"))
    )
    (comp (ref "Q49")
      (value "BCX70K")
      (footprint "SOT23")
      (description "TRANS NPN AF 45V SOT-23")
      (fields (field (name "MANUFACTURER") "Fairchild Semiconductor") (field (name "SOURCE") "Digikey"))
      (libsource (lib "ScoreBoard") (part "QS/BCX70K00Z"))
    )
    (comp (ref "Q50")
      (value "BCX70K")
      (footprint "SOT23")
      (description "TRANS NPN AF 45V SOT-23")
      (fields (field (name "MANUFACTURER") "Fairchild Semiconductor") (field (name "SOURCE") "Digikey"))
      (libsource (lib "ScoreBoard") (part "QS/BCX70K00Z"))
    )
    (comp (ref "Q51")
      (value "BCX70K")
      (footprint "SOT23")
      (description "TRANS NPN AF 45V SOT-23")
      (fields (field (name "MANUFACTURER") "Fairchild Semiconductor") (field (name "SOURCE") "Digikey"))
      (libsource (lib "ScoreBoard") (part "QS/BCX70K00Z"))
    )
    (comp (ref "Q55")
      (value "BCX70K")
      (footprint "SOT23")
      (description "TRANS NPN AF 45V SOT-23")
      (fields (field (name "MANUFACTURER") "Fairchild Semiconductor") (field (name "SOURCE") "Digikey"))
      (libsource (lib "ScoreBoard") (part "QS/BCX70K00Z"))
    )
    (comp (ref "Q56")
      (value "BCX70K")
      (footprint "SOT23")
      (description "TRANS NPN AF 45V SOT-23")
      (fields (field (name "MANUFACTURER") "Fairchild Semiconductor") (field (name "SOURCE") "Digikey"))
      (libsource (lib "ScoreBoard") (part "QS/BCX70K00Z"))
    )
    (comp (ref "Q57")
      (value "BCX70K")
      (footprint "SOT23")
      (description "TRANS NPN AF 45V SOT-23")
      (fields (field (name "MANUFACTURER") "Fairchild Semiconductor") (field (name "SOURCE") "Digikey"))
      (libsource (lib "ScoreBoard") (part "QS/BCX70K00Z"))
    )
    (comp (ref "Q61")
      (value "BCX70K")
      (footprint "SOT23")
      (description "TRANS NPN AF 45V SOT-23")
      (fields (field (name "MANUFACTURER") "Fairchild Semiconductor") (field (name "SOURCE") "Digikey"))
      (libsource (lib "ScoreBoard") (part "QS/BCX70K00Z"))
    )
    (comp (ref "Q62")
      (value "BCX70K")
      (footprint "SOT23")
      (description "TRANS NPN AF 45V SOT-23")
      (fields (field (name "MANUFACTURER") "Fairchild Semiconductor") (field (name "SOURCE") "Digikey"))
      (libsource (lib "ScoreBoard") (part "QS/BCX70K00Z"))
    )
    (comp (ref "Q63")
      (value "BCX70K")
      (footprint "SOT23")
      (description "TRANS NPN AF 45V SOT-23")
      (fields (field (name "MANUFACTURER") "Fairchild Semiconductor") (field (name "SOURCE") "Digikey"))
      (libsource (lib "ScoreBoard") (part "QS/BCX70K00Z"))
    )
    (comp (ref "R108")
      (value "5.1k")
      (footprint "R0805")
      (description "RES 5.10K OHM 1/8W 1% 0805 SMD")
      (fields
        (field (name "MANUFACTURER") "Panasonic - ECG")
        (field (name "MANUFACTURER PART NUMBER") "ERJ-6ENF5101V")
      )
      (libsource (lib "eRCL") (part "ERJ-6ENF5101V"))
    )
    (comp (ref "R109")
      (value "5.1k")
      (footprint "R0805")
      (description "RES 5.10K OHM 1/8W 1% 0805 SMD")
      (fields
        (field (name "MANUFACTURER") "Panasonic - ECG")
        (field (name "MANUFACTURER PART NUMBER") "ERJ-6ENF5101V")
      )
      (libsource (lib "eRCL") (part "ERJ-6ENF5101V"))
    )
    (comp (ref "R110")
      (value "5.1k")
      (footprint "R0805")
      (description "RES 5.10K OHM 1/8W 1% 0805 SMD")
      (fields
        (field (name "MANUFACTURER") "Panasonic - ECG")
        (field (name "MANUFACTURER PART NUMBER") "ERJ-6ENF5101V")
      )
      (libsource (lib "eRCL") (part "ERJ-6ENF5101V"))
    )
    (comp (ref "R114")
      (value "120")
      (footprint "R1206")
      (description "RES 120 OHM 1/4W 1% 1206 SMD")
      (fields
        (field (name "MANUFACTURER") "Panasonic - ECG")
        (field (name "MANUFACTURER PART NUMBER") "ERJ-8ENF1200V")
      )
      (libsource (lib "eRCL") (part "ERJ-8ENF1200V"))
    )
    (comp (ref "R115")
      (value "120")
      (footprint "R1206")
      (description "RES 120 OHM 1/4W 1% 1206 SMD")
      (fields
        (field (name "MANUFACTURER") "Panasonic - ECG")
        (field (name "MANUFACTURER PART NUMBER") "ERJ-8ENF1200V")
      )
      (libsource (lib "eRCL") (part "ERJ-8ENF1200V"))
    )
    (comp (ref "R116")
      (value "120")
      (footprint "R1206")
      (description "RES 120 OHM 1/4W 1% 1206 SMD")
      (fields
        (field (name "MANUFACTURER") "Panasonic - ECG")
        (field (name "MANUFACTURER PART NUMBER") "ERJ-8ENF1200V")
      )
      (libsource (lib "eRCL") (part "ERJ-8ENF1200V"))
    )
    (comp (ref "R120")
      (value "120")
      (footprint "R1206")
      (description "RES 120 OHM 1/4W 1% 1206 SMD")
      (fields
        (field (name "MANUFACTURER") "Panasonic - ECG")
        (field (name "MANUFACTURER PART NUMBER") "ERJ-8ENF1200V")
      )
      (libsource (lib "eRCL") (part "ERJ-8ENF1200V"))
    )
    (comp (ref "R121")
      (value "120")
      (footprint "R1206")
      (description "RES 120 OHM 1/4W 1% 1206 SMD")
      (fields
        (field (name "MANUFACTURER") "Panasonic - ECG")
        (field (name "MANUFACTURER PART NUMBER") "ERJ-8ENF1200V")
      )
      (libsource (lib "eRCL") (part "ERJ-8ENF1200V"))
    )
    (comp (ref "R122")
      (value "120")
      (footprint "R1206")
      (description "RES 120 OHM 1/4W 1% 1206 SMD")
      (fields
        (field (name "MANUFACTURER") "Panasonic - ECG")
        (field (name "MANUFACTURER PART NUMBER") "ERJ-8ENF1200V")
      )
      (libsource (lib "eRCL") (part "ERJ-8ENF1200V"))
    )
    (comp (ref "R126")
      (value "5.1k")
      (footprint "R0805")
      (description "RES 5.10K OHM 1/8W 1% 0805 SMD")
      (fields
        (field (name "MANUFACTURER") "Panasonic - ECG")
        (field (name "MANUFACTURER PART NUMBER") "ERJ-6ENF5101V")
      )
      (libsource (lib "eRCL") (part "ERJ-6ENF5101V"))
    )
    (comp (ref "R127")
      (value "5.1k")
      (footprint "R0805")
      (description "RES 5.10K OHM 1/8W 1% 0805 SMD")
      (fields
        (field (name "MANUFACTURER") "Panasonic - ECG")
        (field (name "MANUFACTURER PART NUMBER") "ERJ-6ENF5101V")
      )
      (libsource (lib "eRCL") (part "ERJ-6ENF5101V"))
    )
    (comp (ref "R128")
      (value "5.1k")
      (footprint "R0805")
      (description "RES 5.10K OHM 1/8W 1% 0805 SMD")
      (fields
        (field (name "MANUFACTURER") "Panasonic - ECG")
        (field (name "MANUFACTURER PART NUMBER") "ERJ-6ENF5101V")
      )
      (libsource (lib "eRCL") (part "ERJ-6ENF5101V"))
    )
    (comp (ref "R132")
      (value "120")
      (footprint "R1206")
      (description "RES 120 OHM 1/4W 1% 1206 SMD")
      (fields
        (field (name "MANUFACTURER") "Panasonic - ECG")
        (field (name "MANUFACTURER PART NUMBER") "ERJ-8ENF1200V")
      )
      (libsource (lib "eRCL") (part "ERJ-8ENF1200V"))
    )
    (comp (ref "R133")
      (value "120")
      (footprint "R1206")
      (description "RES 120 OHM 1/4W 1% 1206 SMD")
      (fields
        (field (name "MANUFACTURER") "Panasonic - ECG")
        (field (name "MANUFACTURER PART NUMBER") "ERJ-8ENF1200V")
      )
      (libsource (lib "eRCL") (part "ERJ-8ENF1200V"))
    )
    (comp (ref "R134")
      (value "120")
      (footprint "R1206")
      (description "RES 120 OHM 1/4W 1% 1206 SMD")
      (fields
        (field (name "MANUFACTURER") "Panasonic - ECG")
        (field (name "MANUFACTURER PART NUMBER") "ERJ-8ENF1200V")
      )
      (libsource (lib "eRCL") (part "ERJ-8ENF1200V"))
    )
    (comp (ref "R138")
      (value "120")
      (footprint "R1206")
      (description "RES 120 OHM 1/4W 1% 1206 SMD")
      (fields
        (field (name "MANUFACTURER") "Panasonic - ECG")
        (field (name "MANUFACTURER PART NUMBER") "ERJ-8ENF1200V")
      )
      (libsource (lib "eRCL") (part "ERJ-8ENF1200V"))
    )
    (comp (ref "R139")
      (value "120")
      (footprint "R1206")
      (description "RES 120 OHM 1/4W 1% 1206 SMD")
      (fields
        (field (name "MANUFACTURER") "Panasonic - ECG")
        (field (name "MANUFACTURER PART NUMBER") "ERJ-8ENF1200V")
      )
      (libsource (lib "eRCL") (part "ERJ-8ENF1200V"))
    )
    (comp (ref "R140")
      (value "120")
      (footprint "R1206")
      (description "RES 120 OHM 1/4W 1% 1206 SMD")
      (fields
        (field (name "MANUFACTURER") "Panasonic - ECG")
        (field (name "MANUFACTURER PART NUMBER") "ERJ-8ENF1200V")
      )
      (libsource (lib "eRCL") (part "ERJ-8ENF1200V"))
    )
    (comp (ref "R144")
      (value "5.1k")
      (footprint "R0805")
      (description "RES 5.10K OHM 1/8W 1% 0805 SMD")
      (fields
        (field (name "MANUFACTURER") "Panasonic - ECG")
        (field (name "MANUFACTURER PART NUMBER") "ERJ-6ENF5101V")
      )
      (libsource (lib "eRCL") (part "ERJ-6ENF5101V"))
    )
    (comp (ref "R145")
      (value "5.1k")
      (footprint "R0805")
      (description "RES 5.10K OHM 1/8W 1% 0805 SMD")
      (fields
        (field (name "MANUFACTURER") "Panasonic - ECG")
        (field (name "MANUFACTURER PART NUMBER") "ERJ-6ENF5101V")
      )
      (libsource (lib "eRCL") (part "ERJ-6ENF5101V"))
    )
    (comp (ref "R146")
      (value "5.1k")
      (footprint "R0805")
      (description "RES 5.10K OHM 1/8W 1% 0805 SMD")
      (fields
        (field (name "MANUFACTURER") "Panasonic - ECG")
        (field (name "MANUFACTURER PART NUMBER") "ERJ-6ENF5101V")
      )
      (libsource (lib "eRCL") (part "ERJ-6ENF5101V"))
    )
    (comp (ref "R150")
      (value "120")
      (footprint "R1206")
      (description "RES 120 OHM 1/4W 1% 1206 SMD")
      (fields
        (field (name "MANUFACTURER") "Panasonic - ECG")
        (field (name "MANUFACTURER PART NUMBER") "ERJ-8ENF1200V")
      )
      (libsource (lib "eRCL") (part "ERJ-8ENF1200V"))
    )
    (comp (ref "R151")
      (value "120")
      (footprint "R1206")
      (description "RES 120 OHM 1/4W 1% 1206 SMD")
      (fields
        (field (name "MANUFACTURER") "Panasonic - ECG")
        (field (name "MANUFACTURER PART NUMBER") "ERJ-8ENF1200V")
      )
      (libsource (lib "eRCL") (part "ERJ-8ENF1200V"))
    )
    (comp (ref "R152")
      (value "120")
      (footprint "R1206")
      (description "RES 120 OHM 1/4W 1% 1206 SMD")
      (fields
        (field (name "MANUFACTURER") "Panasonic - ECG")
        (field (name "MANUFACTURER PART NUMBER") "ERJ-8ENF1200V")
      )
      (libsource (lib "eRCL") (part "ERJ-8ENF1200V"))
    )
    (comp (ref "R156")
      (value "120")
      (footprint "R1206")
      (description "RES 120 OHM 1/4W 1% 1206 SMD")
      (fields
        (field (name "MANUFACTURER") "Panasonic - ECG")
        (field (name "MANUFACTURER PART NUMBER") "ERJ-8ENF1200V")
      )
      (libsource (lib "eRCL") (part "ERJ-8ENF1200V"))
    )
    (comp (ref "R157")
      (value "120")
      (footprint "R1206")
      (description "RES 120 OHM 1/4W 1% 1206 SMD")
      (fields
        (field (name "MANUFACTURER") "Panasonic - ECG")
        (field (name "MANUFACTURER PART NUMBER") "ERJ-8ENF1200V")
      )
      (libsource (lib "eRCL") (part "ERJ-8ENF1200V"))
    )
    (comp (ref "R158")
      (value "120")
      (footprint "R1206")
      (description "RES 120 OHM 1/4W 1% 1206 SMD")
      (fields
        (field (name "MANUFACTURER") "Panasonic - ECG")
        (field (name "MANUFACTURER PART NUMBER") "ERJ-8ENF1200V")
      )
      (libsource (lib "eRCL") (part "ERJ-8ENF1200V"))
    )
    (comp (ref "R162")
      (value "5.1k")
      (footprint "R0805")
      (description "RES 5.10K OHM 1/8W 1% 0805 SMD")
      (fields
        (field (name "MANUFACTURER") "Panasonic - ECG")
        (field (name "MANUFACTURER PART NUMBER") "ERJ-6ENF5101V")
      )
      (libsource (lib "eRCL") (part "ERJ-6ENF5101V"))
    )
    (comp (ref "R163")
      (value "5.1k")
      (footprint "R0805")
      (description "RES 5.10K OHM 1/8W 1% 0805 SMD")
      (fields
        (field (name "MANUFACTURER") "Panasonic - ECG")
        (field (name "MANUFACTURER PART NUMBER") "ERJ-6ENF5101V")
      )
      (libsource (lib "eRCL") (part "ERJ-6ENF5101V"))
    )
    (comp (ref "R164")
      (value "5.1k")
      (footprint "R0805")
      (description "RES 5.10K OHM 1/8W 1% 0805 SMD")
      (fields
        (field (name "MANUFACTURER") "Panasonic - ECG")
        (field (name "MANUFACTURER PART NUMBER") "ERJ-6ENF5101V")
      )
      (libsource (lib "eRCL") (part "ERJ-6ENF5101V"))
    )
    (comp (ref "R168")
      (value "120")
      (footprint "R1206")
      (description "RES 120 OHM 1/4W 1% 1206 SMD")
      (fields
        (field (name "MANUFACTURER") "Panasonic - ECG")
        (field (name "MANUFACTURER PART NUMBER") "ERJ-8ENF1200V")
      )
      (libsource (lib "eRCL") (part "ERJ-8ENF1200V"))
    )
    (comp (ref "R169")
      (value "120")
      (footprint "R1206")
      (description "RES 120 OHM 1/4W 1% 1206 SMD")
      (fields
        (field (name "MANUFACTURER") "Panasonic - ECG")
        (field (name "MANUFACTURER PART NUMBER") "ERJ-8ENF1200V")
      )
      (libsource (lib "eRCL") (part "ERJ-8ENF1200V"))
    )
    (comp (ref "R170")
      (value "120")
      (footprint "R1206")
      (description "RES 120 OHM 1/4W 1% 1206 SMD")
      (fields
        (field (name "MANUFACTURER") "Panasonic - ECG")
        (field (name "MANUFACTURER PART NUMBER") "ERJ-8ENF1200V")
      )
      (libsource (lib "eRCL") (part "ERJ-8ENF1200V"))
    )
    (comp (ref "R174")
      (value "120")
      (footprint "R1206")
      (description "RES 120 OHM 1/4W 1% 1206 SMD")
      (fields
        (field (name "MANUFACTURER") "Panasonic - ECG")
        (field (name "MANUFACTURER PART NUMBER") "ERJ-8ENF1200V")
      )
      (libsource (lib "eRCL") (part "ERJ-8ENF1200V"))
    )
    (comp (ref "R175")
      (value "120")
      (footprint "R1206")
      (description "RES 120 OHM 1/4W 1% 1206 SMD")
      (fields
        (field (name "MANUFACTURER") "Panasonic - ECG")
        (field (name "MANUFACTURER PART NUMBER") "ERJ-8ENF1200V")
      )
      (libsource (lib "eRCL") (part "ERJ-8ENF1200V"))
    )
    (comp (ref "R176")
      (value "120")
      (footprint "R1206")
      (description "RES 120 OHM 1/4W 1% 1206 SMD")
      (fields
        (field (name "MANUFACTURER") "Panasonic - ECG")
        (field (name "MANUFACTURER PART NUMBER") "ERJ-8ENF1200V")
      )
      (libsource (lib "eRCL") (part "ERJ-8ENF1200V"))
    )
    (comp (ref "R180")
      (value "5.1k")
      (footprint "R0805")
      (description "RES 5.10K OHM 1/8W 1% 0805 SMD")
      (fields
        (field (name "MANUFACTURER") "Panasonic - ECG")
        (field (name "MANUFACTURER PART NUMBER") "ERJ-6ENF5101V")
      )
      (libsource (lib "eRCL") (part "ERJ-6ENF5101V"))
    )
    (comp (ref "R181")
      (value "5.1k")
      (footprint "R0805")
      (description "RES 5.10K OHM 1/8W 1% 0805 SMD")
      (fields
        (field (name "MANUFACTURER") "Panasonic - ECG")
        (field (name "MANUFACTURER PART NUMBER") "ERJ-6ENF5101V")
      )
      (libsource (lib "eRCL") (part "ERJ-6ENF5101V"))
    )
    (comp (ref "R182")
      (value "5.1k")
      (footprint "R0805")
      (description "RES 5.10K OHM 1/8W 1% 0805 SMD")
      (fields
        (field (name "MANUFACTURER") "Panasonic - ECG")
        (field (name "MANUFACTURER PART NUMBER") "ERJ-6ENF5101V")
      )
      (libsource (lib "eRCL") (part "ERJ-6ENF5101V"))
    )
    (comp (ref "R186")
      (value "120")
      (footprint "R1206")
      (description "RES 120 OHM 1/4W 1% 1206 SMD")
      (fields
        (field (name "MANUFACTURER") "Panasonic - ECG")
        (field (name "MANUFACTURER PART NUMBER") "ERJ-8ENF1200V")
      )
      (libsource (lib "eRCL") (part "ERJ-8ENF1200V"))
    )
    (comp (ref "R187")
      (value "120")
      (footprint "R1206")
      (description "RES 120 OHM 1/4W 1% 1206 SMD")
      (fields
        (field (name "MANUFACTURER") "Panasonic - ECG")
        (field (name "MANUFACTURER PART NUMBER") "ERJ-8ENF1200V")
      )
      (libsource (lib "eRCL") (part "ERJ-8ENF1200V"))
    )
    (comp (ref "R188")
      (value "120")
      (footprint "R1206")
      (description "RES 120 OHM 1/4W 1% 1206 SMD")
      (fields
        (field (name "MANUFACTURER") "Panasonic - ECG")
        (field (name "MANUFACTURER PART NUMBER") "ERJ-8ENF1200V")
      )
      (libsource (lib "eRCL") (part "ERJ-8ENF1200V"))
    )
    (comp (ref "R192")
      (value "120")
      (footprint "R1206")
      (description "RES 120 OHM 1/4W 1% 1206 SMD")
      (fields
        (field (name "MANUFACTURER") "Panasonic - ECG")
        (field (name "MANUFACTURER PART NUMBER") "ERJ-8ENF1200V")
      )
      (libsource (lib "eRCL") (part "ERJ-8ENF1200V"))
    )
    (comp (ref "R193")
      (value "120")
      (footprint "R1206")
      (description "RES 120 OHM 1/4W 1% 1206 SMD")
      (fields
        (field (name "MANUFACTURER") "Panasonic - ECG")
        (field (name "MANUFACTURER PART NUMBER") "ERJ-8ENF1200V")
      )
      (libsource (lib "eRCL") (part "ERJ-8ENF1200V"))
    )
    (comp (ref "R194")
      (value "120")
      (footprint "R1206")
      (description "RES 120 OHM 1/4W 1% 1206 SMD")
      (fields
        (field (name "MANUFACTURER") "Panasonic - ECG")
        (field (name "MANUFACTURER PART NUMBER") "ERJ-8ENF1200V")
      )
      (libsource (lib "eRCL") (part "ERJ-8ENF1200V"))
    )
    (comp (ref "R198")
      (value "5.1k")
      (footprint "R0805")
      (description "RES 5.10K OHM 1/8W 1% 0805 SMD")
      (fields
        (field (name "MANUFACTURER") "Panasonic - ECG")
        (field (name "MANUFACTURER PART NUMBER") "ERJ-6ENF5101V")
      )
      (libsource (lib "eRCL") (part "ERJ-6ENF5101V"))
    )
    (comp (ref "R199")
      (value "5.1k")
      (footprint "R0805")
      (description "RES 5.10K OHM 1/8W 1% 0805 SMD")
      (fields
        (field (name "MANUFACTURER") "Panasonic - ECG")
        (field (name "MANUFACTURER PART NUMBER") "ERJ-6ENF5101V")
      )
      (libsource (lib "eRCL") (part "ERJ-6ENF5101V"))
    )
    (comp (ref "R200")
      (value "5.1k")
      (footprint "R0805")
      (description "RES 5.10K OHM 1/8W 1% 0805 SMD")
      (fields
        (field (name "MANUFACTURER") "Panasonic - ECG")
        (field (name "MANUFACTURER PART NUMBER") "ERJ-6ENF5101V")
      )
      (libsource (lib "eRCL") (part "ERJ-6ENF5101V"))
    )
    (comp (ref "R204")
      (value "120")
      (footprint "R1206")
      (description "RES 120 OHM 1/4W 1% 1206 SMD")
      (fields
        (field (name "MANUFACTURER") "Panasonic - ECG")
        (field (name "MANUFACTURER PART NUMBER") "ERJ-8ENF1200V")
      )
      (libsource (lib "eRCL") (part "ERJ-8ENF1200V"))
    )
    (comp (ref "R205")
      (value "120")
      (footprint "R1206")
      (description "RES 120 OHM 1/4W 1% 1206 SMD")
      (fields
        (field (name "MANUFACTURER") "Panasonic - ECG")
        (field (name "MANUFACTURER PART NUMBER") "ERJ-8ENF1200V")
      )
      (libsource (lib "eRCL") (part "ERJ-8ENF1200V"))
    )
    (comp (ref "R206")
      (value "120")
      (footprint "R1206")
      (description "RES 120 OHM 1/4W 1% 1206 SMD")
      (fields
        (field (name "MANUFACTURER") "Panasonic - ECG")
        (field (name "MANUFACTURER PART NUMBER") "ERJ-8ENF1200V")
      )
      (libsource (lib "eRCL") (part "ERJ-8ENF1200V"))
    )
    (comp (ref "R210")
      (value "120")
      (footprint "R1206")
      (description "RES 120 OHM 1/4W 1% 1206 SMD")
      (fields
        (field (name "MANUFACTURER") "Panasonic - ECG")
        (field (name "MANUFACTURER PART NUMBER") "ERJ-8ENF1200V")
      )
      (libsource (lib "eRCL") (part "ERJ-8ENF1200V"))
    )
    (comp (ref "R211")
      (value "120")
      (footprint "R1206")
      (description "RES 120 OHM 1/4W 1% 1206 SMD")
      (fields
        (field (name "MANUFACTURER") "Panasonic - ECG")
        (field (name "MANUFACTURER PART NUMBER") "ERJ-8ENF1200V")
      )
      (libsource (lib "eRCL") (part "ERJ-8ENF1200V"))
    )
    (comp (ref "R212")
      (value "120")
      (footprint "R1206")
      (description "RES 120 OHM 1/4W 1% 1206 SMD")
      (fields
        (field (name "MANUFACTURER") "Panasonic - ECG")
        (field (name "MANUFACTURER PART NUMBER") "ERJ-8ENF1200V")
      )
      (libsource (lib "eRCL") (part "ERJ-8ENF1200V"))
    )
    (comp (ref "R216")
      (value "5.1k")
      (footprint "R0805")
      (description "RES 5.10K OHM 1/8W 1% 0805 SMD")
      (fields
        (field (name "MANUFACTURER") "Panasonic - ECG")
        (field (name "MANUFACTURER PART NUMBER") "ERJ-6ENF5101V")
      )
      (libsource (lib "eRCL") (part "ERJ-6ENF5101V"))
    )
    (comp (ref "R217")
      (value "5.1k")
      (footprint "R0805")
      (description "RES 5.10K OHM 1/8W 1% 0805 SMD")
      (fields
        (field (name "MANUFACTURER") "Panasonic - ECG")
        (field (name "MANUFACTURER PART NUMBER") "ERJ-6ENF5101V")
      )
      (libsource (lib "eRCL") (part "ERJ-6ENF5101V"))
    )
    (comp (ref "R218")
      (value "5.1k")
      (footprint "R0805")
      (description "RES 5.10K OHM 1/8W 1% 0805 SMD")
      (fields
        (field (name "MANUFACTURER") "Panasonic - ECG")
        (field (name "MANUFACTURER PART NUMBER") "ERJ-6ENF5101V")
      )
      (libsource (lib "eRCL") (part "ERJ-6ENF5101V"))
    )
    (comp (ref "R222")
      (value "120")
      (footprint "R1206")
      (description "RES 120 OHM 1/4W 1% 1206 SMD")
      (fields
        (field (name "MANUFACTURER") "Panasonic - ECG")
        (field (name "MANUFACTURER PART NUMBER") "ERJ-8ENF1200V")
      )
      (libsource (lib "eRCL") (part "ERJ-8ENF1200V"))
    )
    (comp (ref "R223")
      (value "120")
      (footprint "R1206")
      (description "RES 120 OHM 1/4W 1% 1206 SMD")
      (fields
        (field (name "MANUFACTURER") "Panasonic - ECG")
        (field (name "MANUFACTURER PART NUMBER") "ERJ-8ENF1200V")
      )
      (libsource (lib "eRCL") (part "ERJ-8ENF1200V"))
    )
    (comp (ref "R224")
      (value "120")
      (footprint "R1206")
      (description "RES 120 OHM 1/4W 1% 1206 SMD")
      (fields
        (field (name "MANUFACTURER") "Panasonic - ECG")
        (field (name "MANUFACTURER PART NUMBER") "ERJ-8ENF1200V")
      )
      (libsource (lib "eRCL") (part "ERJ-8ENF1200V"))
    )
    (comp (ref "R228")
      (value "120")
      (footprint "R1206")
      (description "RES 120 OHM 1/4W 1% 1206 SMD")
      (fields
        (field (name "MANUFACTURER") "Panasonic - ECG")
        (field (name "MANUFACTURER PART NUMBER") "ERJ-8ENF1200V")
      )
      (libsource (lib "eRCL") (part "ERJ-8ENF1200V"))
    )
    (comp (ref "R229")
      (value "120")
      (footprint "R1206")
      (description "RES 120 OHM 1/4W 1% 1206 SMD")
      (fields
        (field (name "MANUFACTURER") "Panasonic - ECG")
        (field (name "MANUFACTURER PART NUMBER") "ERJ-8ENF1200V")
      )
      (libsource (lib "eRCL") (part "ERJ-8ENF1200V"))
    )
    (comp (ref "R230")
      (value "120")
      (footprint "R1206")
      (description "RES 120 OHM 1/4W 1% 1206 SMD")
      (fields
        (field (name "MANUFACTURER") "Panasonic - ECG")
        (field (name "MANUFACTURER PART NUMBER") "ERJ-8ENF1200V")
      )
      (libsource (lib "eRCL") (part "ERJ-8ENF1200V"))
    )
    (comp (ref "U22")
      (value "IS/SN74HC573DWZ")
      (footprint "SOIC300-20")
      (description "Octal D-Type Transparent Latch with 3-State Outputs")
      (fields
        (field (name "MANUFACTURER") "NXP Semiconductors")
        (field (name "MANUFACTURER PART NUMBER") "74HC573D-T")
        (field (name "SOURCE") "Digikey")
      )
      (libsource (lib "ScoreBoard") (part "IS/SN74HC573DWZ"))
    )
    (comp (ref "U23")
      (value "IS/SN74HC573DWZ")
      (footprint "SOIC300-20")
      (description "Octal D-Type Transparent Latch with 3-State Outputs")
      (fields
        (field (name "MANUFACTURER") "NXP Semiconductors")
        (field (name "MANUFACTURER PART NUMBER") "74HC573D-T")
        (field (name "SOURCE") "Digikey")
      )
      (libsource (lib "ScoreBoard") (part "IS/SN74HC573DWZ"))
    )
    (comp (ref "U24")
      (value "IS/SN74HC573DWZ")
      (footprint "SOIC300-20")
      (description "Octal D-Type Transparent Latch with 3-State Outputs")
      (fields
        (field (name "MANUFACTURER") "NXP Semiconductors")
        (field (name "MANUFACTURER PART NUMBER") "74HC573D-T")
        (field (name "SOURCE") "Digikey")
      )
      (libsource (lib "ScoreBoard") (part "IS/SN74HC573DWZ"))
    )
  )
  (nets
    (net (code "1") (name "/8V") (class "Default")
      (node (ref "DS103") (pin "1") (pinfunction "A_1") (pintype "passive"))
      (node (ref "DS105") (pin "1") (pinfunction "A_1") (pintype "passive"))
      (node (ref "DS107") (pin "1") (pinfunction "A_1") (pintype "passive"))
      (node (ref "DS11") (pin "1") (pinfunction "A_1") (pintype "passive"))
      (node (ref "DS115") (pin "1") (pinfunction "A_1") (pintype "passive"))
      (node (ref "DS117") (pin "1") (pinfunction "A_1") (pintype "passive"))
      (node (ref "DS119") (pin "1") (pinfunction "A_1") (pintype "passive"))
      (node (ref "DS127") (pin "1") (pinfunction "A_1") (pintype "passive"))
      (node (ref "DS129") (pin "1") (pinfunction "A_1") (pintype "passive"))
      (node (ref "DS131") (pin "1") (pinfunction "A_1") (pintype "passive"))
      (node (ref "DS139") (pin "1") (pinfunction "A_1") (pintype "passive"))
      (node (ref "DS141") (pin "1") (pinfunction "A_1") (pintype "passive"))
      (node (ref "DS143") (pin "1") (pinfunction "A_1") (pintype "passive"))
      (node (ref "DS151") (pin "1") (pinfunction "A_1") (pintype "passive"))
      (node (ref "DS153") (pin "1") (pinfunction "A_1") (pintype "passive"))
      (node (ref "DS155") (pin "1") (pinfunction "A_1") (pintype "passive"))
      (node (ref "DS163") (pin "1") (pinfunction "A_1") (pintype "passive"))
      (node (ref "DS165") (pin "1") (pinfunction "A_1") (pintype "passive"))
      (node (ref "DS167") (pin "1") (pinfunction "A_1") (pintype "passive"))
      (node (ref "DS19") (pin "1") (pinfunction "A_1") (pintype "passive"))
      (node (ref "DS21") (pin "1") (pinfunction "A_1") (pintype "passive"))
      (node (ref "DS23") (pin "1") (pinfunction "A_1") (pintype "passive"))
      (node (ref "DS31") (pin "1") (pinfunction "A_1") (pintype "passive"))
      (node (ref "DS33") (pin "1") (pinfunction "A_1") (pintype "passive"))
      (node (ref "DS35") (pin "1") (pinfunction "A_1") (pintype "passive"))
      (node (ref "DS43") (pin "1") (pinfunction "A_1") (pintype "passive"))
      (node (ref "DS45") (pin "1") (pinfunction "A_1") (pintype "passive"))
      (node (ref "DS47") (pin "1") (pinfunction "A_1") (pintype "passive"))
      (node (ref "DS55") (pin "1") (pinfunction "A_1") (pintype "passive"))
      (node (ref "DS57") (pin "1") (pinfunction "A_1") (pintype "passive"))
      (node (ref "DS59") (pin "1") (pinfunction "A_1") (pintype "passive"))
      (node (ref "DS67") (pin "1") (pinfunction "A_1") (pintype "passive"))
      (node (ref "DS69") (pin "1") (pinfunction "A_1") (pintype "passive"))
      (node (ref "DS7") (pin "1") (pinfunction "A_1") (pintype "passive"))
      (node (ref "DS71") (pin "1") (pinfunction "A_1") (pintype "passive"))
      (node (ref "DS79") (pin "1") (pinfunction "A_1") (pintype "passive"))
      (node (ref "DS81") (pin "1") (pinfunction "A_1") (pintype "passive"))
      (node (ref "DS83") (pin "1") (pinfunction "A_1") (pintype "passive"))
      (node (ref "DS9") (pin "1") (pinfunction "A_1") (pintype "passive"))
      (node (ref "DS91") (pin "1") (pinfunction "A_1") (pintype "passive"))
      (node (ref "DS93") (pin "1") (pinfunction "A_1") (pintype "passive"))
      (node (ref "DS95") (pin "1") (pinfunction "A_1") (pintype "passive"))
    )
    (net (code "2") (name "/CLK3") (class "Default")
      (node (ref "U22") (pin "11") (pinfunction "LE_11") (pintype "input"))
    )
    (net (code "3") (name "/CLK4") (class "Default")
      (node (ref "U23") (pin "11") (pinfunction "LE_11") (pintype "input"))
    )
    (net (code "4") (name "/CLK5") (class "Default")
      (node (ref "U24") (pin "11") (pinfunction "LE_11") (pintype "input"))
    )
    (net (code "5") (name "/D0") (class "Default")
      (node (ref "U22") (pin "2") (pinfunction "D1_2") (pintype "input"))
      (node (ref "U23") (pin "2") (pinfunction "D1_2") (pintype "input"))
      (node (ref "U24") (pin "2") (pinfunction "D1_2") (pintype "input"))
    )
    (net (code "6") (name "/D1") (class "Default")
      (node (ref "U22") (pin "3") (pinfunction "D2_3") (pintype "input"))
      (node (ref "U23") (pin "3") (pinfunction "D2_3") (pintype "input"))
      (node (ref "U24") (pin "3") (pinfunction "D2_3") (pintype "input"))
    )
    (net (code "7") (name "/D2") (class "Default")
      (node (ref "U22") (pin "4") (pinfunction "D3_4") (pintype "input"))
      (node (ref "U23") (pin "4") (pinfunction "D3_4") (pintype "input"))
      (node (ref "U24") (pin "4") (pinfunction "D3_4") (pintype "input"))
    )
    (net (code "8") (name "/D3") (class "Default")
      (node (ref "U22") (pin "5") (pinfunction "D4_5") (pintype "input"))
      (node (ref "U23") (pin "5") (pinfunction "D4_5") (pintype "input"))
      (node (ref "U24") (pin "5") (pinfunction "D4_5") (pintype "input"))
    )
    (net (code "9") (name "/D4") (class "Default")
      (node (ref "U22") (pin "6") (pinfunction "D5_6") (pintype "input"))
      (node (ref "U23") (pin "6") (pinfunction "D5_6") (pintype "input"))
      (node (ref "U24") (pin "6") (pinfunction "D5_6") (pintype "input"))
    )
    (net (code "10") (name "/D5") (class "Default")
      (node (ref "U22") (pin "7") (pinfunction "D6_7") (pintype "input"))
      (node (ref "U23") (pin "7") (pinfunction "D6_7") (pintype "input"))
      (node (ref "U24") (pin "7") (pinfunction "D6_7") (pintype "input"))
    )
    (net (code "11") (name "/D6") (class "Default")
      (node (ref "U22") (pin "8") (pinfunction "D7_8") (pintype "input"))
      (node (ref "U23") (pin "8") (pinfunction "D7_8") (pintype "input"))
      (node (ref "U24") (pin "8") (pinfunction "D7_8") (pintype "input"))
    )
    (net (code "12") (name "/D7") (class "Default")
      (node (ref "U22") (pin "9") (pinfunction "D8_9") (pintype "input"))
      (node (ref "U23") (pin "9") (pinfunction "D8_9") (pintype "input"))
      (node (ref "U24") (pin "9") (pinfunction "D8_9") (pintype "input"))
    )
    (net (code "13") (name "/LAMP3") (class "Default")
      (node (ref "U22") (pin "12") (pinfunction "Q8_12") (pintype "tri_state"))
    )
    (net (code "14") (name "/LAMP4") (class "Default")
      (node (ref "U23") (pin "12") (pinfunction "Q8_12") (pintype "tri_state"))
    )
    (net (code "15") (name "/LAMP5") (class "Default")
      (node (ref "U24") (pin "12") (pinfunction "Q8_12") (pintype "tri_state"))
    )
    (net (code "16") (name "/LED_OE") (class "Default")
      (node (ref "U22") (pin "1") (pinfunction "~{OE}_1") (pintype "input"))
      (node (ref "U23") (pin "1") (pinfunction "~{OE}_1") (pintype "input"))
      (node (ref "U24") (pin "1") (pinfunction "~{OE}_1") (pintype "input"))
    )
    (net (code "17") (name "GND") (class "Default")
      (node (ref "C50") (pin "2") (pinfunction "2_2") (pintype "passive"))
      (node (ref "C51") (pin "2") (pinfunction "2_2") (pintype "passive"))
      (node (ref "C52") (pin "2") (pinfunction "2_2") (pintype "passive"))
      (node (ref "Q25") (pin "2") (pinfunction "E_2") (pintype "passive"))
      (node (ref "Q26") (pin "2") (pinfunction "E_2") (pintype "passive"))
      (node (ref "Q27") (pin "2") (pinfunction "E_2") (pintype "passive"))
      (node (ref "Q31") (pin "2") (pinfunction "E_2") (pintype "passive"))
      (node (ref "Q32") (pin "2") (pinfunction "E_2") (pintype "passive"))
      (node (ref "Q33") (pin "2") (pinfunction "E_2") (pintype "passive"))
      (node (ref "Q37") (pin "2") (pinfunction "E_2") (pintype "passive"))
      (node (ref "Q38") (pin "2") (pinfunction "E_2") (pintype "passive"))
      (node (ref "Q39") (pin "2") (pinfunction "E_2") (pintype "passive"))
      (node (ref "Q43") (pin "2") (pinfunction "E_2") (pintype "passive"))
      (node (ref "Q44") (pin "2") (pinfunction "E_2") (pintype "passive"))
      (node (ref "Q45") (pin "2") (pinfunction "E_2") (pintype "passive"))
      (node (ref "Q49") (pin "2") (pinfunction "E_2") (pintype "passive"))
      (node (ref "Q50") (pin "2") (pinfunction "E_2") (pintype "passive"))
      (node (ref "Q51") (pin "2") (pinfunction "E_2") (pintype "passive"))
      (node (ref "Q55") (pin "2") (pinfunction "E_2") (pintype "passive"))
      (node (ref "Q56") (pin "2") (pinfunction "E_2") (pintype "passive"))
      (node (ref "Q57") (pin "2") (pinfunction "E_2") (pintype "passive"))
      (node (ref "Q61") (pin "2") (pinfunction "E_2") (pintype "passive"))
      (node (ref "Q62") (pin "2") (pinfunction "E_2") (pintype "passive"))
      (node (ref "Q63") (pin "2") (pinfunction "E_2") (pintype "passive"))
      (node (ref "U22") (pin "10") (pinfunction "GND_10") (pintype "power_in"))
      (node (ref "U23") (pin "10") (pinfunction "GND_10") (pintype "power_in"))
      (node (ref "U24") (pin "10") (pinfunction "GND_10") (pintype "power_in"))
    )
    (net (code "18") (name "Net-(DS7-K)") (class "Default")
      (node (ref "DS7") (pin "2") (pinfunction "K_2") (pintype "passive"))
      (node (ref "DS8") (pin "1") (pinfunction "A_1") (pintype "passive"))
    )
    (net (code "19") (name "Net-(DS8-K)") (class "Default")
      (node (ref "DS8") (pin "2") (pinfunction "K_2") (pintype "passive"))
      (node (ref "R114") (pin "2") (pinfunction "2_2") (pintype "passive"))
    )
    (net (code "20") (name "Net-(DS10-A)") (class "Default")
      (node (ref "DS10") (pin "1") (pinfunction "A_1") (pintype "passive"))
      (node (ref "DS9") (pin "2") (pinfunction "K_2") (pintype "passive"))
    )
    (net (code "21") (name "Net-(DS10-K)") (class "Default")
      (node (ref "DS10") (pin "2") (pinfunction "K_2") (pintype "passive"))
      (node (ref "R115") (pin "2") (pinfunction "2_2") (pintype "passive"))
    )
    (net (code "22") (name "Net-(DS11-K)") (class "Default")
      (node (ref "DS11") (pin "2") (pinfunction "K_2") (pintype "passive"))
      (node (ref "DS12") (pin "1") (pinfunction "A_1") (pintype "passive"))
    )
    (net (code "23") (name "Net-(DS12-K)") (class "Default")
      (node (ref "DS12") (pin "2") (pinfunction "K_2") (pintype "passive"))
      (node (ref "R116") (pin "2") (pinfunction "2_2") (pintype "passive"))
    )
    (net (code "24") (name "Net-(DS19-K)") (class "Default")
      (node (ref "DS19") (pin "2") (pinfunction "K_2") (pintype "passive"))
      (node (ref "DS20") (pin "1") (pinfunction "A_1") (pintype "passive"))
    )
    (net (code "25") (name "Net-(DS20-K)") (class "Default")
      (node (ref "DS20") (pin "2") (pinfunction "K_2") (pintype "passive"))
      (node (ref "R120") (pin "2") (pinfunction "2_2") (pintype "passive"))
    )
    (net (code "26") (name "Net-(DS21-K)") (class "Default")
      (node (ref "DS21") (pin "2") (pinfunction "K_2") (pintype "passive"))
      (node (ref "DS22") (pin "1") (pinfunction "A_1") (pintype "passive"))
    )
    (net (code "27") (name "Net-(DS22-K)") (class "Default")
      (node (ref "DS22") (pin "2") (pinfunction "K_2") (pintype "passive"))
      (node (ref "R121") (pin "2") (pinfunction "2_2") (pintype "passive"))
    )
    (net (code "28") (name "Net-(DS23-K)") (class "Default")
      (node (ref "DS23") (pin "2") (pinfunction "K_2") (pintype "passive"))
      (node (ref "DS24") (pin "1") (pinfunction "A_1") (pintype "passive"))
    )
    (net (code "29") (name "Net-(DS24-K)") (class "Default")
      (node (ref "DS24") (pin "2") (pinfunction "K_2") (pintype "passive"))
      (node (ref "R122") (pin "2") (pinfunction "2_2") (pintype "passive"))
    )
    (net (code "30") (name "Net-(DS31-K)") (class "Default")
      (node (ref "DS31") (pin "2") (pinfunction "K_2") (pintype "passive"))
      (node (ref "DS32") (pin "1") (pinfunction "A_1") (pintype "passive"))
    )
    (net (code "31") (name "Net-(DS32-K)") (class "Default")
      (node (ref "DS32") (pin "2") (pinfunction "K_2") (pintype "passive"))
      (node (ref "R132") (pin "2") (pinfunction "2_2") (pintype "passive"))
    )
    (net (code "32") (name "Net-(DS33-K)") (class "Default")
      (node (ref "DS33") (pin "2") (pinfunction "K_2") (pintype "passive"))
      (node (ref "DS34") (pin "1") (pinfunction "A_1") (pintype "passive"))
    )
    (net (code "33") (name "Net-(DS34-K)") (class "Default")
      (node (ref "DS34") (pin "2") (pinfunction "K_2") (pintype "passive"))
      (node (ref "R133") (pin "2") (pinfunction "2_2") (pintype "passive"))
    )
    (net (code "34") (name "Net-(DS35-K)") (class "Default")
      (node (ref "DS35") (pin "2") (pinfunction "K_2") (pintype "passive"))
      (node (ref "DS36") (pin "1") (pinfunction "A_1") (pintype "passive"))
    )
    (net (code "35") (name "Net-(DS36-K)") (class "Default")
      (node (ref "DS36") (pin "2") (pinfunction "K_2") (pintype "passive"))
      (node (ref "R134") (pin "2") (pinfunction "2_2") (pintype "passive"))
    )
    (net (code "36") (name "Net-(DS43-K)") (class "Default")
      (node (ref "DS43") (pin "2") (pinfunction "K_2") (pintype "passive"))
      (node (ref "DS44") (pin "1") (pinfunction "A_1") (pintype "passive"))
    )
    (net (code "37") (name "Net-(DS44-K)") (class "Default")
      (node (ref "DS44") (pin "2") (pinfunction "K_2") (pintype "passive"))
      (node (ref "R138") (pin "2") (pinfunction "2_2") (pintype "passive"))
    )
    (net (code "38") (name "Net-(DS45-K)") (class "Default")
      (node (ref "DS45") (pin "2") (pinfunction "K_2") (pintype "passive"))
      (node (ref "DS46") (pin "1") (pinfunction "A_1") (pintype "passive"))
    )
    (net (code "39") (name "Net-(DS46-K)") (class "Default")
      (node (ref "DS46") (pin "2") (pinfunction "K_2") (pintype "passive"))
      (node (ref "R139") (pin "2") (pinfunction "2_2") (pintype "passive"))
    )
    (net (code "40") (name "Net-(DS47-K)") (class "Default")
      (node (ref "DS47") (pin "2") (pinfunction "K_2") (pintype "passive"))
      (node (ref "DS48") (pin "1") (pinfunction "A_1") (pintype "passive"))
    )
    (net (code "41") (name "Net-(DS48-K)") (class "Default")
      (node (ref "DS48") (pin "2") (pinfunction "K_2") (pintype "passive"))
      (node (ref "R140") (pin "2") (pinfunction "2_2") (pintype "passive"))
    )
    (net (code "42") (name "Net-(DS55-K)") (class "Default")
      (node (ref "DS55") (pin "2") (pinfunction "K_2") (pintype "passive"))
      (node (ref "DS56") (pin "1") (pinfunction "A_1") (pintype "passive"))
    )
    (net (code "43") (name "Net-(DS56-K)") (class "Default")
      (node (ref "DS56") (pin "2") (pinfunction "K_2") (pintype "passive"))
      (node (ref "R150") (pin "2") (pinfunction "2_2") (pintype "passive"))
    )
    (net (code "44") (name "Net-(DS57-K)") (class "Default")
      (node (ref "DS57") (pin "2") (pinfunction "K_2") (pintype "passive"))
      (node (ref "DS58") (pin "1") (pinfunction "A_1") (pintype "passive"))
    )
    (net (code "45") (name "Net-(DS58-K)") (class "Default")
      (node (ref "DS58") (pin "2") (pinfunction "K_2") (pintype "passive"))
      (node (ref "R151") (pin "2") (pinfunction "2_2") (pintype "passive"))
    )
    (net (code "46") (name "Net-(DS59-K)") (class "Default")
      (node (ref "DS59") (pin "2") (pinfunction "K_2") (pintype "passive"))
      (node (ref "DS60") (pin "1") (pinfunction "A_1") (pintype "passive"))
    )
    (net (code "47") (name "Net-(DS60-K)") (class "Default")
      (node (ref "DS60") (pin "2") (pinfunction "K_2") (pintype "passive"))
      (node (ref "R152") (pin "2") (pinfunction "2_2") (pintype "passive"))
    )
    (net (code "48") (name "Net-(DS67-K)") (class "Default")
      (node (ref "DS67") (pin "2") (pinfunction "K_2") (pintype "passive"))
      (node (ref "DS68") (pin "1") (pinfunction "A_1") (pintype "passive"))
    )
    (net (code "49") (name "Net-(DS68-K)") (class "Default")
      (node (ref "DS68") (pin "2") (pinfunction "K_2") (pintype "passive"))
      (node (ref "R156") (pin "2") (pinfunction "2_2") (pintype "passive"))
    )
    (net (code "50") (name "Net-(DS69-K)") (class "Default")
      (node (ref "DS69") (pin "2") (pinfunction "K_2") (pintype "passive"))
      (node (ref "DS70") (pin "1") (pinfunction "A_1") (pintype "passive"))
    )
    (net (code "51") (name "Net-(DS70-K)") (class "Default")
      (node (ref "DS70") (pin "2") (pinfunction "K_2") (pintype "passive"))
      (node (ref "R157") (pin "2") (pinfunction "2_2") (pintype "passive"))
    )
    (net (code "52") (name "Net-(DS71-K)") (class "Default")
      (node (ref "DS71") (pin "2") (pinfunction "K_2") (pintype "passive"))
      (node (ref "DS72") (pin "1") (pinfunction "A_1") (pintype "passive"))
    )
    (net (code "53") (name "Net-(DS72-K)") (class "Default")
      (node (ref "DS72") (pin "2") (pinfunction "K_2") (pintype "passive"))
      (node (ref "R158") (pin "2") (pinfunction "2_2") (pintype "passive"))
    )
    (net (code "54") (name "Net-(DS79-K)") (class "Default")
      (node (ref "DS79") (pin "2") (pinfunction "K_2") (pintype "passive"))
      (node (ref "DS80") (pin "1") (pinfunction "A_1") (pintype "passive"))
    )
    (net (code "55") (name "Net-(DS80-K)") (class "Default")
      (node (ref "DS80") (pin "2") (pinfunction "K_2") (pintype "passive"))
      (node (ref "R168") (pin "2") (pinfunction "2_2") (pintype "passive"))
    )
    (net (code "56") (name "Net-(DS81-K)") (class "Default")
      (node (ref "DS81") (pin "2") (pinfunction "K_2") (pintype "passive"))
      (node (ref "DS82") (pin "1") (pinfunction "A_1") (pintype "passive"))
    )
    (net (code "57") (name "Net-(DS82-K)") (class "Default")
      (node (ref "DS82") (pin "2") (pinfunction "K_2") (pintype "passive"))
      (node (ref "R169") (pin "2") (pinfunction "2_2") (pintype "passive"))
    )
    (net (code "58") (name "Net-(DS83-K)") (class "Default")
      (node (ref "DS83") (pin "2") (pinfunction "K_2") (pintype "passive"))
      (node (ref "DS84") (pin "1") (pinfunction "A_1") (pintype "passive"))
    )
    (net (code "59") (name "Net-(DS84-K)") (class "Default")
      (node (ref "DS84") (pin "2") (pinfunction "K_2") (pintype "passive"))
      (node (ref "R170") (pin "2") (pinfunction "2_2") (pintype "passive"))
    )
    (net (code "60") (name "Net-(DS91-K)") (class "Default")
      (node (ref "DS91") (pin "2") (pinfunction "K_2") (pintype "passive"))
      (node (ref "DS92") (pin "1") (pinfunction "A_1") (pintype "passive"))
    )
    (net (code "61") (name "Net-(DS92-K)") (class "Default")
      (node (ref "DS92") (pin "2") (pinfunction "K_2") (pintype "passive"))
      (node (ref "R174") (pin "2") (pinfunction "2_2") (pintype "passive"))
    )
    (net (code "62") (name "Net-(DS93-K)") (class "Default")
      (node (ref "DS93") (pin "2") (pinfunction "K_2") (pintype "passive"))
      (node (ref "DS94") (pin "1") (pinfunction "A_1") (pintype "passive"))
    )
    (net (code "63") (name "Net-(DS94-K)") (class "Default")
      (node (ref "DS94") (pin "2") (pinfunction "K_2") (pintype "passive"))
      (node (ref "R175") (pin "2") (pinfunction "2_2") (pintype "passive"))
    )
    (net (code "64") (name "Net-(DS95-K)") (class "Default")
      (node (ref "DS95") (pin "2") (pinfunction "K_2") (pintype "passive"))
      (node (ref "DS96") (pin "1") (pinfunction "A_1") (pintype "passive"))
    )
    (net (code "65") (name "Net-(DS96-K)") (class "Default")
      (node (ref "DS96") (pin "2") (pinfunction "K_2") (pintype "passive"))
      (node (ref "R176") (pin "2") (pinfunction "2_2") (pintype "passive"))
    )
    (net (code "66") (name "Net-(DS103-K)") (class "Default")
      (node (ref "DS103") (pin "2") (pinfunction "K_2") (pintype "passive"))
      (node (ref "DS104") (pin "1") (pinfunction "A_1") (pintype "passive"))
    )
    (net (code "67") (name "Net-(DS104-K)") (class "Default")
      (node (ref "DS104") (pin "2") (pinfunction "K_2") (pintype "passive"))
      (node (ref "R186") (pin "2") (pinfunction "2_2") (pintype "passive"))
    )
    (net (code "68") (name "Net-(DS105-K)") (class "Default")
      (node (ref "DS105") (pin "2") (pinfunction "K_2") (pintype "passive"))
      (node (ref "DS106") (pin "1") (pinfunction "A_1") (pintype "passive"))
    )
    (net (code "69") (name "Net-(DS106-K)") (class "Default")
      (node (ref "DS106") (pin "2") (pinfunction "K_2") (pintype "passive"))
      (node (ref "R187") (pin "2") (pinfunction "2_2") (pintype "passive"))
    )
    (net (code "70") (name "Net-(DS107-K)") (class "Default")
      (node (ref "DS107") (pin "2") (pinfunction "K_2") (pintype "passive"))
      (node (ref "DS108") (pin "1") (pinfunction "A_1") (pintype "passive"))
    )
    (net (code "71") (name "Net-(DS108-K)") (class "Default")
      (node (ref "DS108") (pin "2") (pinfunction "K_2") (pintype "passive"))
      (node (ref "R188") (pin "2") (pinfunction "2_2") (pintype "passive"))
    )
    (net (code "72") (name "Net-(DS115-K)") (class "Default")
      (node (ref "DS115") (pin "2") (pinfunction "K_2") (pintype "passive"))
      (node (ref "DS116") (pin "1") (pinfunction "A_1") (pintype "passive"))
    )
    (net (code "73") (name "Net-(DS116-K)") (class "Default")
      (node (ref "DS116") (pin "2") (pinfunction "K_2") (pintype "passive"))
      (node (ref "R192") (pin "2") (pinfunction "2_2") (pintype "passive"))
    )
    (net (code "74") (name "Net-(DS117-K)") (class "Default")
      (node (ref "DS117") (pin "2") (pinfunction "K_2") (pintype "passive"))
      (node (ref "DS118") (pin "1") (pinfunction "A_1") (pintype "passive"))
    )
    (net (code "75") (name "Net-(DS118-K)") (class "Default")
      (node (ref "DS118") (pin "2") (pinfunction "K_2") (pintype "passive"))
      (node (ref "R193") (pin "2") (pinfunction "2_2") (pintype "passive"))
    )
    (net (code "76") (name "Net-(DS119-K)") (class "Default")
      (node (ref "DS119") (pin "2") (pinfunction "K_2") (pintype "passive"))
      (node (ref "DS120") (pin "1") (pinfunction "A_1") (pintype "passive"))
    )
    (net (code "77") (name "Net-(DS120-K)") (class "Default")
      (node (ref "DS120") (pin "2") (pinfunction "K_2") (pintype "passive"))
      (node (ref "R194") (pin "2") (pinfunction "2_2") (pintype "passive"))
    )
    (net (code "78") (name "Net-(DS127-K)") (class "Default")
      (node (ref "DS127") (pin "2") (pinfunction "K_2") (pintype "passive"))
      (node (ref "DS128") (pin "1") (pinfunction "A_1") (pintype "passive"))
    )
    (net (code "79") (name "Net-(DS128-K)") (class "Default")
      (node (ref "DS128") (pin "2") (pinfunction "K_2") (pintype "passive"))
      (node (ref "R204") (pin "2") (pinfunction "2_2") (pintype "passive"))
    )
    (net (code "80") (name "Net-(DS129-K)") (class "Default")
      (node (ref "DS129") (pin "2") (pinfunction "K_2") (pintype "passive"))
      (node (ref "DS130") (pin "1") (pinfunction "A_1") (pintype "passive"))
    )
    (net (code "81") (name "Net-(DS130-K)") (class "Default")
      (node (ref "DS130") (pin "2") (pinfunction "K_2") (pintype "passive"))
      (node (ref "R205") (pin "2") (pinfunction "2_2") (pintype "passive"))
    )
    (net (code "82") (name "Net-(DS131-K)") (class "Default")
      (node (ref "DS131") (pin "2") (pinfunction "K_2") (pintype "passive"))
      (node (ref "DS132") (pin "1") (pinfunction "A_1") (pintype "passive"))
    )
    (net (code "83") (name "Net-(DS132-K)") (class "Default")
      (node (ref "DS132") (pin "2") (pinfunction "K_2") (pintype "passive"))
      (node (ref "R206") (pin "2") (pinfunction "2_2") (pintype "passive"))
    )
    (net (code "84") (name "Net-(DS139-K)") (class "Default")
      (node (ref "DS139") (pin "2") (pinfunction "K_2") (pintype "passive"))
      (node (ref "DS140") (pin "1") (pinfunction "A_1") (pintype "passive"))
    )
    (net (code "85") (name "Net-(DS140-K)") (class "Default")
      (node (ref "DS140") (pin "2") (pinfunction "K_2") (pintype "passive"))
      (node (ref "R210") (pin "2") (pinfunction "2_2") (pintype "passive"))
    )
    (net (code "86") (name "Net-(DS141-K)") (class "Default")
      (node (ref "DS141") (pin "2") (pinfunction "K_2") (pintype "passive"))
      (node (ref "DS142") (pin "1") (pinfunction "A_1") (pintype "passive"))
    )
    (net (code "87") (name "Net-(DS142-K)") (class "Default")
      (node (ref "DS142") (pin "2") (pinfunction "K_2") (pintype "passive"))
      (node (ref "R211") (pin "2") (pinfunction "2_2") (pintype "passive"))
    )
    (net (code "88") (name "Net-(DS143-K)") (class "Default")
      (node (ref "DS143") (pin "2") (pinfunction "K_2") (pintype "passive"))
      (node (ref "DS144") (pin "1") (pinfunction "A_1") (pintype "passive"))
    )
    (net (code "89") (name "Net-(DS144-K)") (class "Default")
      (node (ref "DS144") (pin "2") (pinfunction "K_2") (pintype "passive"))
      (node (ref "R212") (pin "2") (pinfunction "2_2") (pintype "passive"))
    )
    (net (code "90") (name "Net-(DS151-K)") (class "Default")
      (node (ref "DS151") (pin "2") (pinfunction "K_2") (pintype "passive"))
      (node (ref "DS152") (pin "1") (pinfunction "A_1") (pintype "passive"))
    )
    (net (code "91") (name "Net-(DS152-K)") (class "Default")
      (node (ref "DS152") (pin "2") (pinfunction "K_2") (pintype "passive"))
      (node (ref "R222") (pin "2") (pinfunction "2_2") (pintype "passive"))
    )
    (net (code "92") (name "Net-(DS153-K)") (class "Default")
      (node (ref "DS153") (pin "2") (pinfunction "K_2") (pintype "passive"))
      (node (ref "DS154") (pin "1") (pinfunction "A_1") (pintype "passive"))
    )
    (net (code "93") (name "Net-(DS154-K)") (class "Default")
      (node (ref "DS154") (pin "2") (pinfunction "K_2") (pintype "passive"))
      (node (ref "R223") (pin "2") (pinfunction "2_2") (pintype "passive"))
    )
    (net (code "94") (name "Net-(DS155-K)") (class "Default")
      (node (ref "DS155") (pin "2") (pinfunction "K_2") (pintype "passive"))
      (node (ref "DS156") (pin "1") (pinfunction "A_1") (pintype "passive"))
    )
    (net (code "95") (name "Net-(DS156-K)") (class "Default")
      (node (ref "DS156") (pin "2") (pinfunction "K_2") (pintype "passive"))
      (node (ref "R224") (pin "2") (pinfunction "2_2") (pintype "passive"))
    )
    (net (code "96") (name "Net-(DS163-K)") (class "Default")
      (node (ref "DS163") (pin "2") (pinfunction "K_2") (pintype "passive"))
      (node (ref "DS164") (pin "1") (pinfunction "A_1") (pintype "passive"))
    )
    (net (code "97") (name "Net-(DS164-K)") (class "Default")
      (node (ref "DS164") (pin "2") (pinfunction "K_2") (pintype "passive"))
      (node (ref "R228") (pin "2") (pinfunction "2_2") (pintype "passive"))
    )
    (net (code "98") (name "Net-(DS165-K)") (class "Default")
      (node (ref "DS165") (pin "2") (pinfunction "K_2") (pintype "passive"))
      (node (ref "DS166") (pin "1") (pinfunction "A_1") (pintype "passive"))
    )
    (net (code "99") (name "Net-(DS166-K)") (class "Default")
      (node (ref "DS166") (pin "2") (pinfunction "K_2") (pintype "passive"))
      (node (ref "R229") (pin "2") (pinfunction "2_2") (pintype "passive"))
    )
    (net (code "100") (name "Net-(DS167-K)") (class "Default")
      (node (ref "DS167") (pin "2") (pinfunction "K_2") (pintype "passive"))
      (node (ref "DS168") (pin "1") (pinfunction "A_1") (pintype "passive"))
    )
    (net (code "101") (name "Net-(DS168-K)") (class "Default")
      (node (ref "DS168") (pin "2") (pinfunction "K_2") (pintype "passive"))
      (node (ref "R230") (pin "2") (pinfunction "2_2") (pintype "passive"))
    )
    (net (code "102") (name "Net-(Q25-B)") (class "Default")
      (node (ref "Q25") (pin "1") (pinfunction "B_1") (pintype "passive"))
      (node (ref "R108") (pin "2") (pinfunction "2_2") (pintype "passive"))
    )
    (net (code "103") (name "Net-(Q25-C)") (class "Default")
      (node (ref "Q25") (pin "3") (pinfunction "C_3") (pintype "passive"))
      (node (ref "R114") (pin "1") (pinfunction "1_1") (pintype "passive"))
      (node (ref "R120") (pin "1") (pinfunction "1_1") (pintype "passive"))
    )
    (net (code "104") (name "Net-(Q26-B)") (class "Default")
      (node (ref "Q26") (pin "1") (pinfunction "B_1") (pintype "passive"))
      (node (ref "R109") (pin "2") (pinfunction "2_2") (pintype "passive"))
    )
    (net (code "105") (name "Net-(Q26-C)") (class "Default")
      (node (ref "Q26") (pin "3") (pinfunction "C_3") (pintype "passive"))
      (node (ref "R115") (pin "1") (pinfunction "1_1") (pintype "passive"))
      (node (ref "R121") (pin "1") (pinfunction "1_1") (pintype "passive"))
    )
    (net (code "106") (name "Net-(Q27-B)") (class "Default")
      (node (ref "Q27") (pin "1") (pinfunction "B_1") (pintype "passive"))
      (node (ref "R110") (pin "2") (pinfunction "2_2") (pintype "passive"))
    )
    (net (code "107") (name "Net-(Q27-C)") (class "Default")
      (node (ref "Q27") (pin "3") (pinfunction "C_3") (pintype "passive"))
      (node (ref "R116") (pin "1") (pinfunction "1_1") (pintype "passive"))
      (node (ref "R122") (pin "1") (pinfunction "1_1") (pintype "passive"))
    )
    (net (code "108") (name "Net-(Q31-B)") (class "Default")
      (node (ref "Q31") (pin "1") (pinfunction "B_1") (pintype "passive"))
      (node (ref "R126") (pin "2") (pinfunction "2_2") (pintype "passive"))
    )
    (net (code "109") (name "Net-(Q31-C)") (class "Default")
      (node (ref "Q31") (pin "3") (pinfunction "C_3") (pintype "passive"))
      (node (ref "R132") (pin "1") (pinfunction "1_1") (pintype "passive"))
      (node (ref "R138") (pin "1") (pinfunction "1_1") (pintype "passive"))
    )
    (net (code "110") (name "Net-(Q32-B)") (class "Default")
      (node (ref "Q32") (pin "1") (pinfunction "B_1") (pintype "passive"))
      (node (ref "R127") (pin "2") (pinfunction "2_2") (pintype "passive"))
    )
    (net (code "111") (name "Net-(Q32-C)") (class "Default")
      (node (ref "Q32") (pin "3") (pinfunction "C_3") (pintype "passive"))
      (node (ref "R133") (pin "1") (pinfunction "1_1") (pintype "passive"))
      (node (ref "R139") (pin "1") (pinfunction "1_1") (pintype "passive"))
    )
    (net (code "112") (name "Net-(Q33-B)") (class "Default")
      (node (ref "Q33") (pin "1") (pinfunction "B_1") (pintype "passive"))
      (node (ref "R128") (pin "2") (pinfunction "2_2") (pintype "passive"))
    )
    (net (code "113") (name "Net-(Q33-C)") (class "Default")
      (node (ref "Q33") (pin "3") (pinfunction "C_3") (pintype "passive"))
      (node (ref "R134") (pin "1") (pinfunction "1_1") (pintype "passive"))
      (node (ref "R140") (pin "1") (pinfunction "1_1") (pintype "passive"))
    )
    (net (code "114") (name "Net-(Q37-B)") (class "Default")
      (node (ref "Q37") (pin "1") (pinfunction "B_1") (pintype "passive"))
      (node (ref "R144") (pin "2") (pinfunction "2_2") (pintype "passive"))
    )
    (net (code "115") (name "Net-(Q37-C)") (class "Default")
      (node (ref "Q37") (pin "3") (pinfunction "C_3") (pintype "passive"))
      (node (ref "R150") (pin "1") (pinfunction "1_1") (pintype "passive"))
      (node (ref "R156") (pin "1") (pinfunction "1_1") (pintype "passive"))
    )
    (net (code "116") (name "Net-(Q38-B)") (class "Default")
      (node (ref "Q38") (pin "1") (pinfunction "B_1") (pintype "passive"))
      (node (ref "R145") (pin "2") (pinfunction "2_2") (pintype "passive"))
    )
    (net (code "117") (name "Net-(Q38-C)") (class "Default")
      (node (ref "Q38") (pin "3") (pinfunction "C_3") (pintype "passive"))
      (node (ref "R151") (pin "1") (pinfunction "1_1") (pintype "passive"))
      (node (ref "R157") (pin "1") (pinfunction "1_1") (pintype "passive"))
    )
    (net (code "118") (name "Net-(Q39-B)") (class "Default")
      (node (ref "Q39") (pin "1") (pinfunction "B_1") (pintype "passive"))
      (node (ref "R146") (pin "2") (pinfunction "2_2") (pintype "passive"))
    )
    (net (code "119") (name "Net-(Q39-C)") (class "Default")
      (node (ref "Q39") (pin "3") (pinfunction "C_3") (pintype "passive"))
      (node (ref "R152") (pin "1") (pinfunction "1_1") (pintype "passive"))
      (node (ref "R158") (pin "1") (pinfunction "1_1") (pintype "passive"))
    )
    (net (code "120") (name "Net-(Q43-B)") (class "Default")
      (node (ref "Q43") (pin "1") (pinfunction "B_1") (pintype "passive"))
      (node (ref "R162") (pin "2") (pinfunction "2_2") (pintype "passive"))
    )
    (net (code "121") (name "Net-(Q43-C)") (class "Default")
      (node (ref "Q43") (pin "3") (pinfunction "C_3") (pintype "passive"))
      (node (ref "R168") (pin "1") (pinfunction "1_1") (pintype "passive"))
      (node (ref "R174") (pin "1") (pinfunction "1_1") (pintype "passive"))
    )
    (net (code "122") (name "Net-(Q44-B)") (class "Default")
      (node (ref "Q44") (pin "1") (pinfunction "B_1") (pintype "passive"))
      (node (ref "R163") (pin "2") (pinfunction "2_2") (pintype "passive"))
    )
    (net (code "123") (name "Net-(Q44-C)") (class "Default")
      (node (ref "Q44") (pin "3") (pinfunction "C_3") (pintype "passive"))
      (node (ref "R169") (pin "1") (pinfunction "1_1") (pintype "passive"))
      (node (ref "R175") (pin "1") (pinfunction "1_1") (pintype "passive"))
    )
    (net (code "124") (name "Net-(Q45-B)") (class "Default")
      (node (ref "Q45") (pin "1") (pinfunction "B_1") (pintype "passive"))
      (node (ref "R164") (pin "2") (pinfunction "2_2") (pintype "passive"))
    )
    (net (code "125") (name "Net-(Q45-C)") (class "Default")
      (node (ref "Q45") (pin "3") (pinfunction "C_3") (pintype "passive"))
      (node (ref "R170") (pin "1") (pinfunction "1_1") (pintype "passive"))
      (node (ref "R176") (pin "1") (pinfunction "1_1") (pintype "passive"))
    )
    (net (code "126") (name "Net-(Q49-B)") (class "Default")
      (node (ref "Q49") (pin "1") (pinfunction "B_1") (pintype "passive"))
      (node (ref "R180") (pin "2") (pinfunction "2_2") (pintype "passive"))
    )
    (net (code "127") (name "Net-(Q49-C)") (class "Default")
      (node (ref "Q49") (pin "3") (pinfunction "C_3") (pintype "passive"))
      (node (ref "R186") (pin "1") (pinfunction "1_1") (pintype "passive"))
      (node (ref "R192") (pin "1") (pinfunction "1_1") (pintype "passive"))
    )
    (net (code "128") (name "Net-(Q50-B)") (class "Default")
      (node (ref "Q50") (pin "1") (pinfunction "B_1") (pintype "passive"))
      (node (ref "R181") (pin "2") (pinfunction "2_2") (pintype "passive"))
    )
    (net (code "129") (name "Net-(Q50-C)") (class "Default")
      (node (ref "Q50") (pin "3") (pinfunction "C_3") (pintype "passive"))
      (node (ref "R187") (pin "1") (pinfunction "1_1") (pintype "passive"))
      (node (ref "R193") (pin "1") (pinfunction "1_1") (pintype "passive"))
    )
    (net (code "130") (name "Net-(Q51-B)") (class "Default")
      (node (ref "Q51") (pin "1") (pinfunction "B_1") (pintype "passive"))
      (node (ref "R182") (pin "2") (pinfunction "2_2") (pintype "passive"))
    )
    (net (code "131") (name "Net-(Q51-C)") (class "Default")
      (node (ref "Q51") (pin "3") (pinfunction "C_3") (pintype "passive"))
      (node (ref "R188") (pin "1") (pinfunction "1_1") (pintype "passive"))
      (node (ref "R194") (pin "1") (pinfunction "1_1") (pintype "passive"))
    )
    (net (code "132") (name "Net-(Q55-B)") (class "Default")
      (node (ref "Q55") (pin "1") (pinfunction "B_1") (pintype "passive"))
      (node (ref "R198") (pin "2") (pinfunction "2_2") (pintype "passive"))
    )
    (net (code "133") (name "Net-(Q55-C)") (class "Default")
      (node (ref "Q55") (pin "3") (pinfunction "C_3") (pintype "passive"))
      (node (ref "R204") (pin "1") (pinfunction "1_1") (pintype "passive"))
      (node (ref "R210") (pin "1") (pinfunction "1_1") (pintype "passive"))
    )
    (net (code "134") (name "Net-(Q56-B)") (class "Default")
      (node (ref "Q56") (pin "1") (pinfunction "B_1") (pintype "passive"))
      (node (ref "R199") (pin "2") (pinfunction "2_2") (pintype "passive"))
    )
    (net (code "135") (name "Net-(Q56-C)") (class "Default")
      (node (ref "Q56") (pin "3") (pinfunction "C_3") (pintype "passive"))
      (node (ref "R205") (pin "1") (pinfunction "1_1") (pintype "passive"))
      (node (ref "R211") (pin "1") (pinfunction "1_1") (pintype "passive"))
    )
    (net (code "136") (name "Net-(Q57-B)") (class "Default")
      (node (ref "Q57") (pin "1") (pinfunction "B_1") (pintype "passive"))
      (node (ref "R200") (pin "2") (pinfunction "2_2") (pintype "passive"))
    )
    (net (code "137") (name "Net-(Q57-C)") (class "Default")
      (node (ref "Q57") (pin "3") (pinfunction "C_3") (pintype "passive"))
      (node (ref "R206") (pin "1") (pinfunction "1_1") (pintype "passive"))
      (node (ref "R212") (pin "1") (pinfunction "1_1") (pintype "passive"))
    )
    (net (code "138") (name "Net-(Q61-B)") (class "Default")
      (node (ref "Q61") (pin "1") (pinfunction "B_1") (pintype "passive"))
      (node (ref "R216") (pin "2") (pinfunction "2_2") (pintype "passive"))
    )
    (net (code "139") (name "Net-(Q61-C)") (class "Default")
      (node (ref "Q61") (pin "3") (pinfunction "C_3") (pintype "passive"))
      (node (ref "R222") (pin "1") (pinfunction "1_1") (pintype "passive"))
      (node (ref "R228") (pin "1") (pinfunction "1_1") (pintype "passive"))
    )
    (net (code "140") (name "Net-(Q62-B)") (class "Default")
      (node (ref "Q62") (pin "1") (pinfunction "B_1") (pintype "passive"))
      (node (ref "R217") (pin "2") (pinfunction "2_2") (pintype "passive"))
    )
    (net (code "141") (name "Net-(Q62-C)") (class "Default")
      (node (ref "Q62") (pin "3") (pinfunction "C_3") (pintype "passive"))
      (node (ref "R223") (pin "1") (pinfunction "1_1") (pintype "passive"))
      (node (ref "R229") (pin "1") (pinfunction "1_1") (pintype "passive"))
    )
    (net (code "142") (name "Net-(Q63-B)") (class "Default")
      (node (ref "Q63") (pin "1") (pinfunction "B_1") (pintype "passive"))
      (node (ref "R218") (pin "2") (pinfunction "2_2") (pintype "passive"))
    )
    (net (code "143") (name "Net-(Q63-C)") (class "Default")
      (node (ref "Q63") (pin "3") (pinfunction "C_3") (pintype "passive"))
      (node (ref "R224") (pin "1") (pinfunction "1_1") (pintype "passive"))
      (node (ref "R230") (pin "1") (pinfunction "1_1") (pintype "passive"))
    )
    (net (code "144") (name "Net-(U22-Q1)") (class "Default")
      (node (ref "R108") (pin "1") (pinfunction "1_1") (pintype "passive"))
      (node (ref "U22") (pin "19") (pinfunction "Q1_19") (pintype "tri_state"))
    )
    (net (code "145") (name "Net-(U22-Q2)") (class "Default")
      (node (ref "R126") (pin "1") (pinfunction "1_1") (pintype "passive"))
      (node (ref "U22") (pin "18") (pinfunction "Q2_18") (pintype "tri_state"))
    )
    (net (code "146") (name "Net-(U22-Q3)") (class "Default")
      (node (ref "R144") (pin "1") (pinfunction "1_1") (pintype "passive"))
      (node (ref "U22") (pin "17") (pinfunction "Q3_17") (pintype "tri_state"))
    )
    (net (code "147") (name "Net-(U22-Q4)") (class "Default")
      (node (ref "R162") (pin "1") (pinfunction "1_1") (pintype "passive"))
      (node (ref "U22") (pin "16") (pinfunction "Q4_16") (pintype "tri_state"))
    )
    (net (code "148") (name "Net-(U22-Q5)") (class "Default")
      (node (ref "R180") (pin "1") (pinfunction "1_1") (pintype "passive"))
      (node (ref "U22") (pin "15") (pinfunction "Q5_15") (pintype "tri_state"))
    )
    (net (code "149") (name "Net-(U22-Q6)") (class "Default")
      (node (ref "R198") (pin "1") (pinfunction "1_1") (pintype "passive"))
      (node (ref "U22") (pin "14") (pinfunction "Q6_14") (pintype "tri_state"))
    )
    (net (code "150") (name "Net-(U22-Q7)") (class "Default")
      (node (ref "R216") (pin "1") (pinfunction "1_1") (pintype "passive"))
      (node (ref "U22") (pin "13") (pinfunction "Q7_13") (pintype "tri_state"))
    )
    (net (code "151") (name "Net-(U23-Q1)") (class "Default")
      (node (ref "R109") (pin "1") (pinfunction "1_1") (pintype "passive"))
      (node (ref "U23") (pin "19") (pinfunction "Q1_19") (pintype "tri_state"))
    )
    (net (code "152") (name "Net-(U23-Q2)") (class "Default")
      (node (ref "R127") (pin "1") (pinfunction "1_1") (pintype "passive"))
      (node (ref "U23") (pin "18") (pinfunction "Q2_18") (pintype "tri_state"))
    )
    (net (code "153") (name "Net-(U23-Q3)") (class "Default")
      (node (ref "R145") (pin "1") (pinfunction "1_1") (pintype "passive"))
      (node (ref "U23") (pin "17") (pinfunction "Q3_17") (pintype "tri_state"))
    )
    (net (code "154") (name "Net-(U23-Q4)") (class "Default")
      (node (ref "R163") (pin "1") (pinfunction "1_1") (pintype "passive"))
      (node (ref "U23") (pin "16") (pinfunction "Q4_16") (pintype "tri_state"))
    )
    (net (code "155") (name "Net-(U23-Q5)") (class "Default")
      (node (ref "R181") (pin "1") (pinfunction "1_1") (pintype "passive"))
      (node (ref "U23") (pin "15") (pinfunction "Q5_15") (pintype "tri_state"))
    )
    (net (code "156") (name "Net-(U23-Q6)") (class "Default")
      (node (ref "R199") (pin "1") (pinfunction "1_1") (pintype "passive"))
      (node (ref "U23") (pin "14") (pinfunction "Q6_14") (pintype "tri_state"))
    )
    (net (code "157") (name "Net-(U23-Q7)") (class "Default")
      (node (ref "R217") (pin "1") (pinfunction "1_1") (pintype "passive"))
      (node (ref "U23") (pin "13") (pinfunction "Q7_13") (pintype "tri_state"))
    )
    (net (code "158") (name "Net-(U24-Q1)") (class "Default")
      (node (ref "R110") (pin "1") (pinfunction "1_1") (pintype "passive"))
      (node (ref "U24") (pin "19") (pinfunction "Q1_19") (pintype "tri_state"))
    )
    (net (code "159") (name "Net-(U24-Q2)") (class "Default")
      (node (ref "R128") (pin "1") (pinfunction "1_1") (pintype "passive"))
      (node (ref "U24") (pin "18") (pinfunction "Q2_18") (pintype "tri_state"))
    )
    (net (code "160") (name "Net-(U24-Q3)") (class "Default")
      (node (ref "R146") (pin "1") (pinfunction "1_1") (pintype "passive"))
      (node (ref "U24") (pin "17") (pinfunction "Q3_17") (pintype "tri_state"))
    )
    (net (code "161") (name "Net-(U24-Q4)") (class "Default")
      (node (ref "R164") (pin "1") (pinfunction "1_1") (pintype "passive"))
      (node (ref "U24") (pin "16") (pinfunction "Q4_16") (pintype "tri_state"))
    )
    (net (code "162") (name "Net-(U24-Q5)") (class "Default")
      (node (ref "R182") (pin "1") (pinfunction "1_1") (pintype "passive"))
      (node (ref "U24") (pin "15") (pinfunction "Q5_15") (pintype "tri_state"))
    )
    (net (code "163") (name "Net-(U24-Q6)") (class "Default")
      (node (ref "R200") (pin "1") (pinfunction "1_1") (pintype "passive"))
      (node (ref "U24") (pin "14") (pinfunction "Q6_14") (pintype "tri_state"))
    )
    (net (code "164") (name "Net-(U24-Q7)") (class "Default")
      (node (ref "R218") (pin "1") (pinfunction "1_1") (pintype "passive"))
      (node (ref "U24") (pin "13") (pinfunction "Q7_13") (pintype "tri_state"))
    )
    (net (code "165") (name "VCC") (class "Default")
      (node (ref "C50") (pin "1") (pinfunction "1_1") (pintype "passive"))
      (node (ref "C51") (pin "1") (pinfunction "1_1") (pintype "passive"))
      (node (ref "C52") (pin "1") (pinfunction "1_1") (pintype "passive"))
      (node (ref "U22") (pin "20") (pinfunction "VCC_20") (pintype "power_in"))
      (node (ref "U23") (pin "20") (pinfunction "VCC_20") (pintype "power_in"))
      (node (ref "U24") (pin "20") (pinfunction "VCC_20") (pintype "power_in"))
    )
  )
)
